# LEDpanelECO.net
KiCad netlist of a schematic drawn in EAGLE
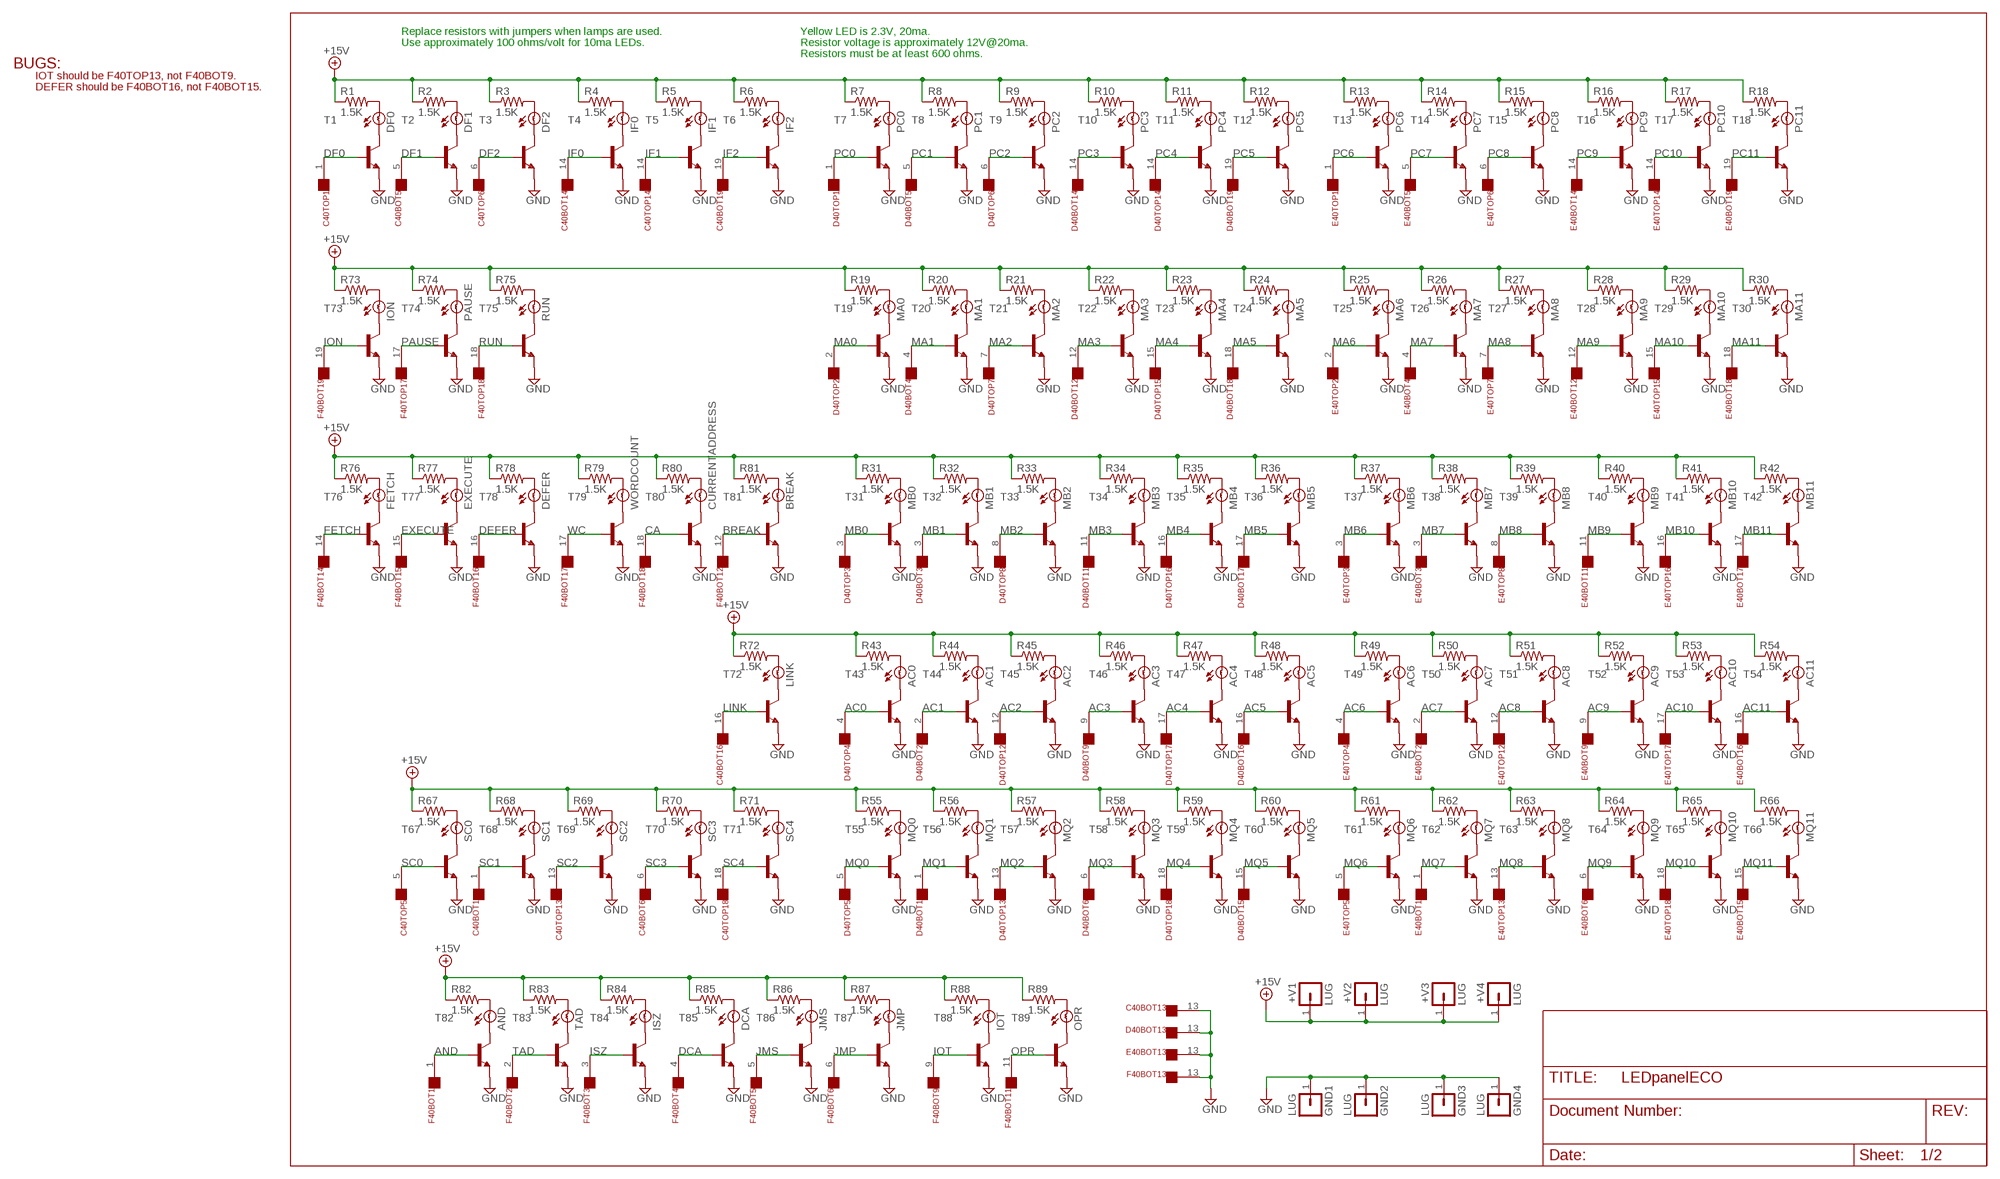
[diagram p0: schematic, sheet 1]
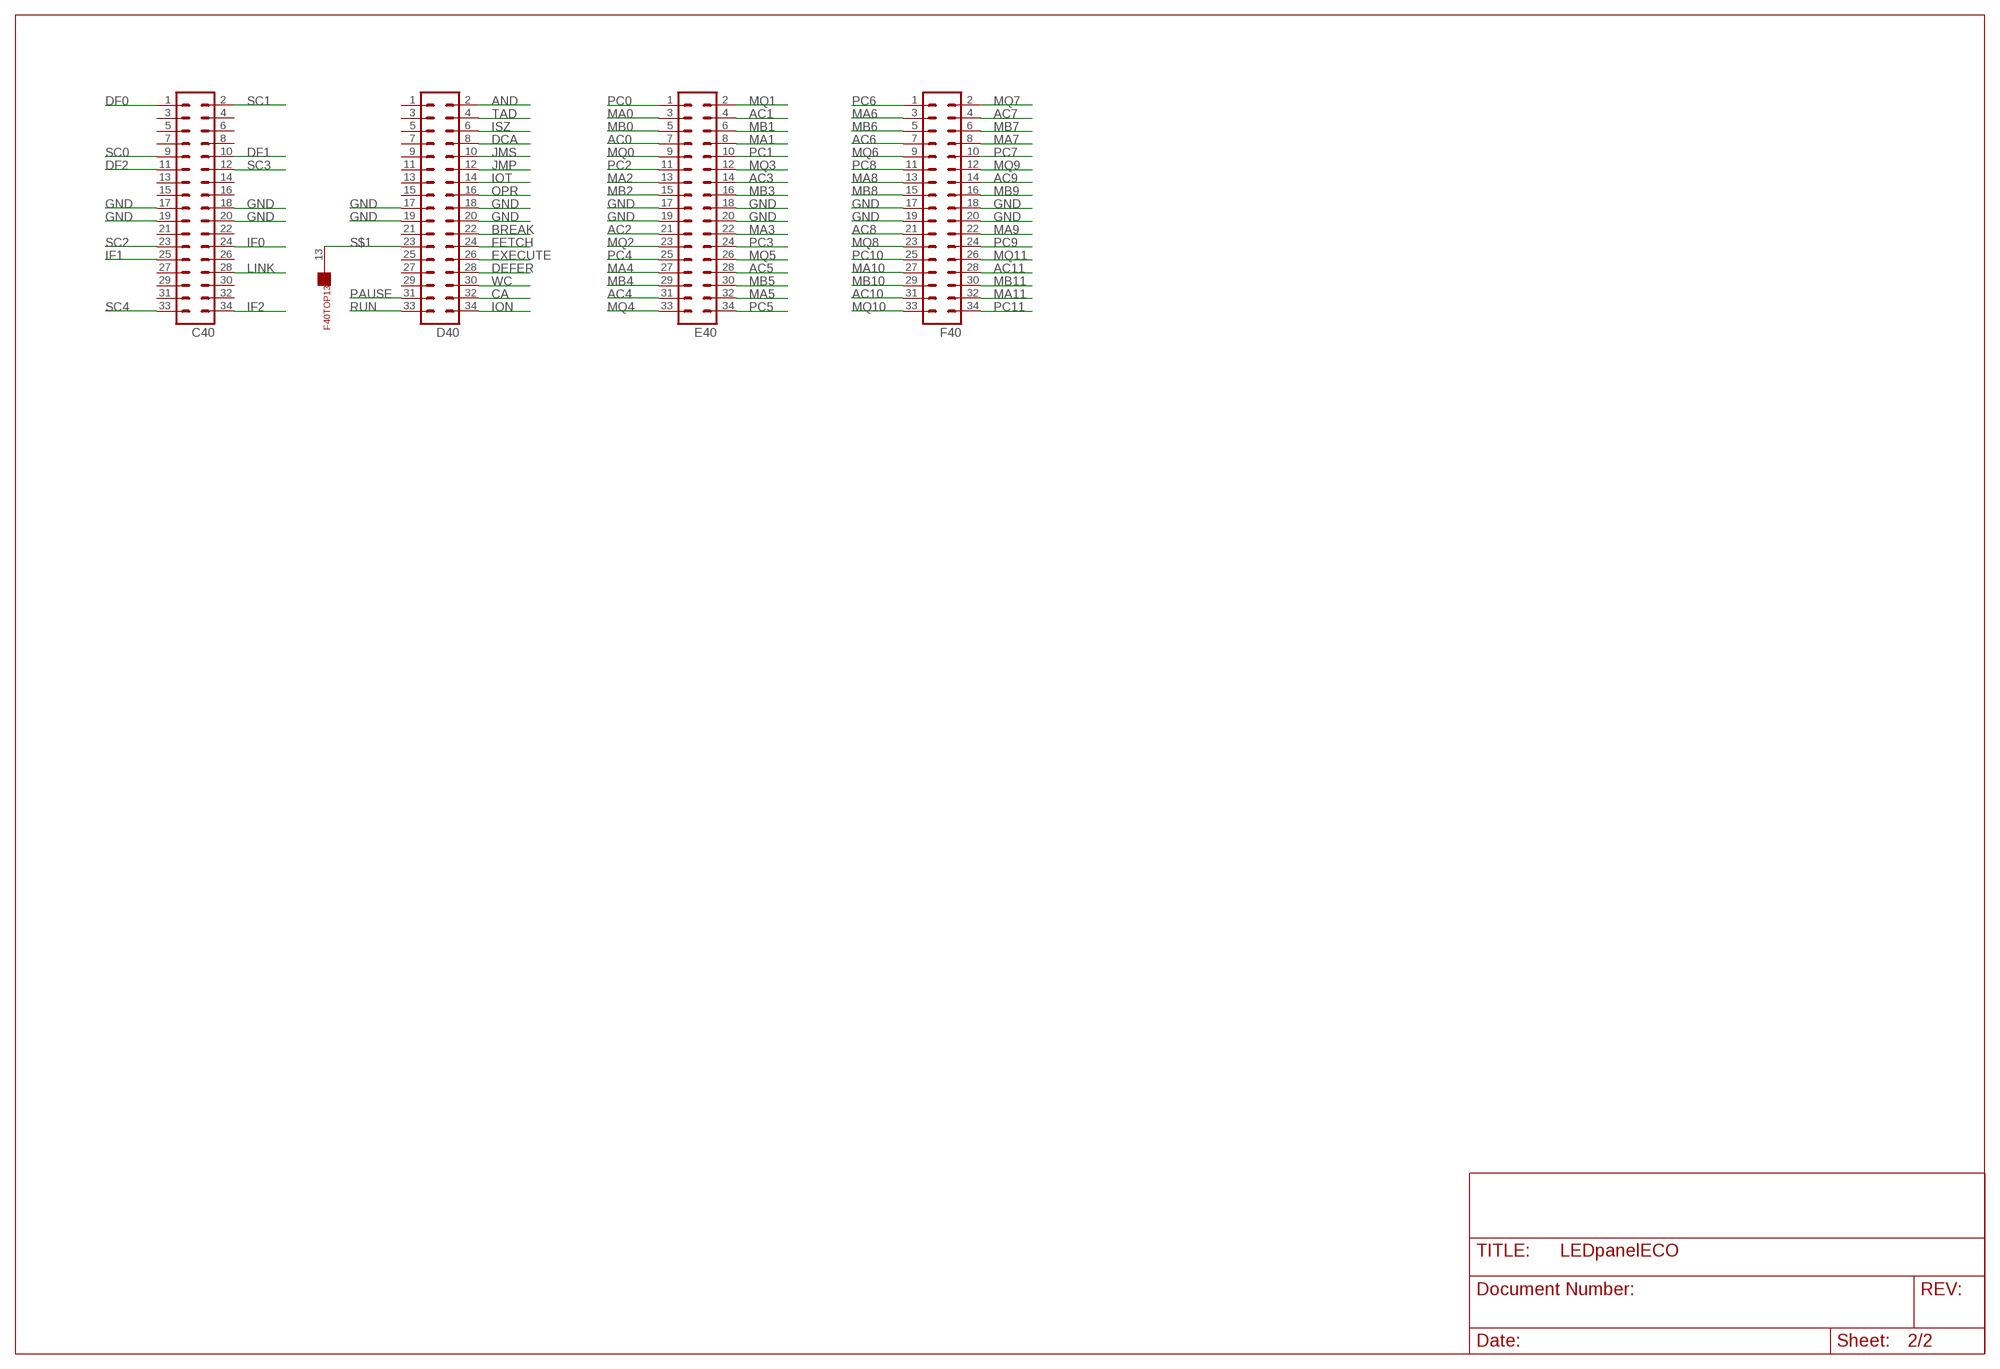
[diagram p1: schematic, sheet 2]

(export (version "E")
  (design (tool "Eeschema 10.0.6"))
  (components
    (comp (ref "C40")
      (value "ML34")
      (footprint "eagle-import:ML34")
      (libsource (lib "eagle-import") (part "ML34"))
    )
    (comp (ref "D40")
      (value "ML34")
      (footprint "eagle-import:ML34")
      (libsource (lib "eagle-import") (part "ML34"))
    )
    (comp (ref "E40")
      (value "ML34")
      (footprint "eagle-import:ML34")
      (libsource (lib "eagle-import") (part "ML34"))
    )
    (comp (ref "F40")
      (value "ML34")
      (footprint "eagle-import:ML34")
      (libsource (lib "eagle-import") (part "ML34"))
    )
    (comp (ref "F40TOP")
      (value "FLEX19")
      (footprint "eagle-import:FLEX19")
      (libsource (lib "eagle-import") (part "FLEX19"))
    )
    (comp (ref "+V1")
      (value "LUG")
      (footprint "eagle-import:SPADELUG")
      (libsource (lib "eagle-import") (part "LUG"))
    )
    (comp (ref "+V2")
      (value "LUG")
      (footprint "eagle-import:SPADELUG")
      (libsource (lib "eagle-import") (part "LUG"))
    )
    (comp (ref "+V3")
      (value "LUG")
      (footprint "eagle-import:SPADELUG")
      (libsource (lib "eagle-import") (part "LUG"))
    )
    (comp (ref "+V4")
      (value "LUG")
      (footprint "eagle-import:SPADELUG")
      (libsource (lib "eagle-import") (part "LUG"))
    )
    (comp (ref "AC0")
      (value "BULB")
      (footprint "eagle-import:BULB")
      (libsource (lib "eagle-import") (part "BULB"))
    )
    (comp (ref "AC1")
      (value "BULB")
      (footprint "eagle-import:BULB")
      (libsource (lib "eagle-import") (part "BULB"))
    )
    (comp (ref "AC2")
      (value "BULB")
      (footprint "eagle-import:BULB")
      (libsource (lib "eagle-import") (part "BULB"))
    )
    (comp (ref "AC3")
      (value "BULB")
      (footprint "eagle-import:BULB")
      (libsource (lib "eagle-import") (part "BULB"))
    )
    (comp (ref "AC4")
      (value "BULB")
      (footprint "eagle-import:BULB")
      (libsource (lib "eagle-import") (part "BULB"))
    )
    (comp (ref "AC5")
      (value "BULB")
      (footprint "eagle-import:BULB")
      (libsource (lib "eagle-import") (part "BULB"))
    )
    (comp (ref "AC6")
      (value "BULB")
      (footprint "eagle-import:BULB")
      (libsource (lib "eagle-import") (part "BULB"))
    )
    (comp (ref "AC7")
      (value "BULB")
      (footprint "eagle-import:BULB")
      (libsource (lib "eagle-import") (part "BULB"))
    )
    (comp (ref "AC8")
      (value "BULB")
      (footprint "eagle-import:BULB")
      (libsource (lib "eagle-import") (part "BULB"))
    )
    (comp (ref "AC9")
      (value "BULB")
      (footprint "eagle-import:BULB")
      (libsource (lib "eagle-import") (part "BULB"))
    )
    (comp (ref "AC10")
      (value "BULB")
      (footprint "eagle-import:BULB")
      (libsource (lib "eagle-import") (part "BULB"))
    )
    (comp (ref "AC11")
      (value "BULB")
      (footprint "eagle-import:BULB")
      (libsource (lib "eagle-import") (part "BULB"))
    )
    (comp (ref "AND")
      (value "BULB")
      (footprint "eagle-import:BULB")
      (libsource (lib "eagle-import") (part "BULB"))
    )
    (comp (ref "BREAK")
      (value "BULB")
      (footprint "eagle-import:BULB")
      (libsource (lib "eagle-import") (part "BULB"))
    )
    (comp (ref "C40BOT")
      (value "FLEX19")
      (footprint "eagle-import:FLEX19")
      (libsource (lib "eagle-import") (part "FLEX19"))
    )
    (comp (ref "C40TOP")
      (value "FLEX19")
      (footprint "eagle-import:FLEX19")
      (libsource (lib "eagle-import") (part "FLEX19"))
    )
    (comp (ref "CURRENTADDRESS")
      (value "BULB")
      (footprint "eagle-import:BULB")
      (libsource (lib "eagle-import") (part "BULB"))
    )
    (comp (ref "D40BOT")
      (value "FLEX19")
      (footprint "eagle-import:FLEX19")
      (libsource (lib "eagle-import") (part "FLEX19"))
    )
    (comp (ref "D40TOP")
      (value "FLEX19")
      (footprint "eagle-import:FLEX19")
      (libsource (lib "eagle-import") (part "FLEX19"))
    )
    (comp (ref "DCA")
      (value "BULB")
      (footprint "eagle-import:BULB")
      (libsource (lib "eagle-import") (part "BULB"))
    )
    (comp (ref "DEFER")
      (value "BULB")
      (footprint "eagle-import:BULB")
      (libsource (lib "eagle-import") (part "BULB"))
    )
    (comp (ref "DF0")
      (value "BULB")
      (footprint "eagle-import:BULB")
      (libsource (lib "eagle-import") (part "BULB"))
    )
    (comp (ref "DF1")
      (value "BULB")
      (footprint "eagle-import:BULB")
      (libsource (lib "eagle-import") (part "BULB"))
    )
    (comp (ref "DF2")
      (value "BULB")
      (footprint "eagle-import:BULB")
      (libsource (lib "eagle-import") (part "BULB"))
    )
    (comp (ref "E40BOT")
      (value "FLEX19")
      (footprint "eagle-import:FLEX19")
      (libsource (lib "eagle-import") (part "FLEX19"))
    )
    (comp (ref "E40TOP")
      (value "FLEX19")
      (footprint "eagle-import:FLEX19")
      (libsource (lib "eagle-import") (part "FLEX19"))
    )
    (comp (ref "EXECUTE")
      (value "BULB")
      (footprint "eagle-import:BULB")
      (libsource (lib "eagle-import") (part "BULB"))
    )
    (comp (ref "F40BOT")
      (value "FLEX19")
      (footprint "eagle-import:FLEX19")
      (libsource (lib "eagle-import") (part "FLEX19"))
    )
    (comp (ref "FETCH")
      (value "BULB")
      (footprint "eagle-import:BULB")
      (libsource (lib "eagle-import") (part "BULB"))
    )
    (comp (ref "GND1")
      (value "LUG")
      (footprint "eagle-import:SPADELUG")
      (libsource (lib "eagle-import") (part "LUG"))
    )
    (comp (ref "GND2")
      (value "LUG")
      (footprint "eagle-import:SPADELUG")
      (libsource (lib "eagle-import") (part "LUG"))
    )
    (comp (ref "GND3")
      (value "LUG")
      (footprint "eagle-import:SPADELUG")
      (libsource (lib "eagle-import") (part "LUG"))
    )
    (comp (ref "GND4")
      (value "LUG")
      (footprint "eagle-import:SPADELUG")
      (libsource (lib "eagle-import") (part "LUG"))
    )
    (comp (ref "IF0")
      (value "BULB")
      (footprint "eagle-import:BULB")
      (libsource (lib "eagle-import") (part "BULB"))
    )
    (comp (ref "IF1")
      (value "BULB")
      (footprint "eagle-import:BULB")
      (libsource (lib "eagle-import") (part "BULB"))
    )
    (comp (ref "IF2")
      (value "BULB")
      (footprint "eagle-import:BULB")
      (libsource (lib "eagle-import") (part "BULB"))
    )
    (comp (ref "ION")
      (value "BULB")
      (footprint "eagle-import:BULB")
      (libsource (lib "eagle-import") (part "BULB"))
    )
    (comp (ref "IOT")
      (value "BULB")
      (footprint "eagle-import:BULB")
      (libsource (lib "eagle-import") (part "BULB"))
    )
    (comp (ref "ISZ")
      (value "BULB")
      (footprint "eagle-import:BULB")
      (libsource (lib "eagle-import") (part "BULB"))
    )
    (comp (ref "JMP")
      (value "BULB")
      (footprint "eagle-import:BULB")
      (libsource (lib "eagle-import") (part "BULB"))
    )
    (comp (ref "JMS")
      (value "BULB")
      (footprint "eagle-import:BULB")
      (libsource (lib "eagle-import") (part "BULB"))
    )
    (comp (ref "LINK")
      (value "BULB")
      (footprint "eagle-import:BULB")
      (libsource (lib "eagle-import") (part "BULB"))
    )
    (comp (ref "MA0")
      (value "BULB")
      (footprint "eagle-import:BULB")
      (libsource (lib "eagle-import") (part "BULB"))
    )
    (comp (ref "MA1")
      (value "BULB")
      (footprint "eagle-import:BULB")
      (libsource (lib "eagle-import") (part "BULB"))
    )
    (comp (ref "MA2")
      (value "BULB")
      (footprint "eagle-import:BULB")
      (libsource (lib "eagle-import") (part "BULB"))
    )
    (comp (ref "MA3")
      (value "BULB")
      (footprint "eagle-import:BULB")
      (libsource (lib "eagle-import") (part "BULB"))
    )
    (comp (ref "MA4")
      (value "BULB")
      (footprint "eagle-import:BULB")
      (libsource (lib "eagle-import") (part "BULB"))
    )
    (comp (ref "MA5")
      (value "BULB")
      (footprint "eagle-import:BULB")
      (libsource (lib "eagle-import") (part "BULB"))
    )
    (comp (ref "MA6")
      (value "BULB")
      (footprint "eagle-import:BULB")
      (libsource (lib "eagle-import") (part "BULB"))
    )
    (comp (ref "MA7")
      (value "BULB")
      (footprint "eagle-import:BULB")
      (libsource (lib "eagle-import") (part "BULB"))
    )
    (comp (ref "MA8")
      (value "BULB")
      (footprint "eagle-import:BULB")
      (libsource (lib "eagle-import") (part "BULB"))
    )
    (comp (ref "MA9")
      (value "BULB")
      (footprint "eagle-import:BULB")
      (libsource (lib "eagle-import") (part "BULB"))
    )
    (comp (ref "MA10")
      (value "BULB")
      (footprint "eagle-import:BULB")
      (libsource (lib "eagle-import") (part "BULB"))
    )
    (comp (ref "MA11")
      (value "BULB")
      (footprint "eagle-import:BULB")
      (libsource (lib "eagle-import") (part "BULB"))
    )
    (comp (ref "MB0")
      (value "BULB")
      (footprint "eagle-import:BULB")
      (libsource (lib "eagle-import") (part "BULB"))
    )
    (comp (ref "MB1")
      (value "BULB")
      (footprint "eagle-import:BULB")
      (libsource (lib "eagle-import") (part "BULB"))
    )
    (comp (ref "MB2")
      (value "BULB")
      (footprint "eagle-import:BULB")
      (libsource (lib "eagle-import") (part "BULB"))
    )
    (comp (ref "MB3")
      (value "BULB")
      (footprint "eagle-import:BULB")
      (libsource (lib "eagle-import") (part "BULB"))
    )
    (comp (ref "MB4")
      (value "BULB")
      (footprint "eagle-import:BULB")
      (libsource (lib "eagle-import") (part "BULB"))
    )
    (comp (ref "MB5")
      (value "BULB")
      (footprint "eagle-import:BULB")
      (libsource (lib "eagle-import") (part "BULB"))
    )
    (comp (ref "MB6")
      (value "BULB")
      (footprint "eagle-import:BULB")
      (libsource (lib "eagle-import") (part "BULB"))
    )
    (comp (ref "MB7")
      (value "BULB")
      (footprint "eagle-import:BULB")
      (libsource (lib "eagle-import") (part "BULB"))
    )
    (comp (ref "MB8")
      (value "BULB")
      (footprint "eagle-import:BULB")
      (libsource (lib "eagle-import") (part "BULB"))
    )
    (comp (ref "MB9")
      (value "BULB")
      (footprint "eagle-import:BULB")
      (libsource (lib "eagle-import") (part "BULB"))
    )
    (comp (ref "MB10")
      (value "BULB")
      (footprint "eagle-import:BULB")
      (libsource (lib "eagle-import") (part "BULB"))
    )
    (comp (ref "MB11")
      (value "BULB")
      (footprint "eagle-import:BULB")
      (libsource (lib "eagle-import") (part "BULB"))
    )
    (comp (ref "MQ0")
      (value "BULB")
      (footprint "eagle-import:BULB")
      (libsource (lib "eagle-import") (part "BULB"))
    )
    (comp (ref "MQ1")
      (value "BULB")
      (footprint "eagle-import:BULB")
      (libsource (lib "eagle-import") (part "BULB"))
    )
    (comp (ref "MQ2")
      (value "BULB")
      (footprint "eagle-import:BULB")
      (libsource (lib "eagle-import") (part "BULB"))
    )
    (comp (ref "MQ3")
      (value "BULB")
      (footprint "eagle-import:BULB")
      (libsource (lib "eagle-import") (part "BULB"))
    )
    (comp (ref "MQ4")
      (value "BULB")
      (footprint "eagle-import:BULB")
      (libsource (lib "eagle-import") (part "BULB"))
    )
    (comp (ref "MQ5")
      (value "BULB")
      (footprint "eagle-import:BULB")
      (libsource (lib "eagle-import") (part "BULB"))
    )
    (comp (ref "MQ6")
      (value "BULB")
      (footprint "eagle-import:BULB")
      (libsource (lib "eagle-import") (part "BULB"))
    )
    (comp (ref "MQ7")
      (value "BULB")
      (footprint "eagle-import:BULB")
      (libsource (lib "eagle-import") (part "BULB"))
    )
    (comp (ref "MQ8")
      (value "BULB")
      (footprint "eagle-import:BULB")
      (libsource (lib "eagle-import") (part "BULB"))
    )
    (comp (ref "MQ9")
      (value "BULB")
      (footprint "eagle-import:BULB")
      (libsource (lib "eagle-import") (part "BULB"))
    )
    (comp (ref "MQ10")
      (value "BULB")
      (footprint "eagle-import:BULB")
      (libsource (lib "eagle-import") (part "BULB"))
    )
    (comp (ref "MQ11")
      (value "BULB")
      (footprint "eagle-import:BULB")
      (libsource (lib "eagle-import") (part "BULB"))
    )
    (comp (ref "OPR")
      (value "BULB")
      (footprint "eagle-import:BULB")
      (libsource (lib "eagle-import") (part "BULB"))
    )
    (comp (ref "PAUSE")
      (value "BULB")
      (footprint "eagle-import:BULB")
      (libsource (lib "eagle-import") (part "BULB"))
    )
    (comp (ref "PC0")
      (value "BULB")
      (footprint "eagle-import:BULB")
      (libsource (lib "eagle-import") (part "BULB"))
    )
    (comp (ref "PC1")
      (value "BULB")
      (footprint "eagle-import:BULB")
      (libsource (lib "eagle-import") (part "BULB"))
    )
    (comp (ref "PC2")
      (value "BULB")
      (footprint "eagle-import:BULB")
      (libsource (lib "eagle-import") (part "BULB"))
    )
    (comp (ref "PC3")
      (value "BULB")
      (footprint "eagle-import:BULB")
      (libsource (lib "eagle-import") (part "BULB"))
    )
    (comp (ref "PC4")
      (value "BULB")
      (footprint "eagle-import:BULB")
      (libsource (lib "eagle-import") (part "BULB"))
    )
    (comp (ref "PC5")
      (value "BULB")
      (footprint "eagle-import:BULB")
      (libsource (lib "eagle-import") (part "BULB"))
    )
    (comp (ref "PC6")
      (value "BULB")
      (footprint "eagle-import:BULB")
      (libsource (lib "eagle-import") (part "BULB"))
    )
    (comp (ref "PC7")
      (value "BULB")
      (footprint "eagle-import:BULB")
      (libsource (lib "eagle-import") (part "BULB"))
    )
    (comp (ref "PC8")
      (value "BULB")
      (footprint "eagle-import:BULB")
      (libsource (lib "eagle-import") (part "BULB"))
    )
    (comp (ref "PC9")
      (value "BULB")
      (footprint "eagle-import:BULB")
      (libsource (lib "eagle-import") (part "BULB"))
    )
    (comp (ref "PC10")
      (value "BULB")
      (footprint "eagle-import:BULB")
      (libsource (lib "eagle-import") (part "BULB"))
    )
    (comp (ref "PC11")
      (value "BULB")
      (footprint "eagle-import:BULB")
      (libsource (lib "eagle-import") (part "BULB"))
    )
    (comp (ref "R1")
      (value "1.5K")
      (footprint "eagle-import:0207_10")
      (libsource (lib "eagle-import") (part "R-US_0207/10"))
    )
    (comp (ref "R2")
      (value "1.5K")
      (footprint "eagle-import:0207_10")
      (libsource (lib "eagle-import") (part "R-US_0207/10"))
    )
    (comp (ref "R3")
      (value "1.5K")
      (footprint "eagle-import:0207_10")
      (libsource (lib "eagle-import") (part "R-US_0207/10"))
    )
    (comp (ref "R4")
      (value "1.5K")
      (footprint "eagle-import:0207_10")
      (libsource (lib "eagle-import") (part "R-US_0207/10"))
    )
    (comp (ref "R5")
      (value "1.5K")
      (footprint "eagle-import:0207_10")
      (libsource (lib "eagle-import") (part "R-US_0207/10"))
    )
    (comp (ref "R6")
      (value "1.5K")
      (footprint "eagle-import:0207_10")
      (libsource (lib "eagle-import") (part "R-US_0207/10"))
    )
    (comp (ref "R7")
      (value "1.5K")
      (footprint "eagle-import:0207_10")
      (libsource (lib "eagle-import") (part "R-US_0207/10"))
    )
    (comp (ref "R8")
      (value "1.5K")
      (footprint "eagle-import:0207_10")
      (libsource (lib "eagle-import") (part "R-US_0207/10"))
    )
    (comp (ref "R9")
      (value "1.5K")
      (footprint "eagle-import:0207_10")
      (libsource (lib "eagle-import") (part "R-US_0207/10"))
    )
    (comp (ref "R10")
      (value "1.5K")
      (footprint "eagle-import:0207_10")
      (libsource (lib "eagle-import") (part "R-US_0207/10"))
    )
    (comp (ref "R11")
      (value "1.5K")
      (footprint "eagle-import:0207_10")
      (libsource (lib "eagle-import") (part "R-US_0207/10"))
    )
    (comp (ref "R12")
      (value "1.5K")
      (footprint "eagle-import:0207_10")
      (libsource (lib "eagle-import") (part "R-US_0207/10"))
    )
    (comp (ref "R13")
      (value "1.5K")
      (footprint "eagle-import:0207_10")
      (libsource (lib "eagle-import") (part "R-US_0207/10"))
    )
    (comp (ref "R14")
      (value "1.5K")
      (footprint "eagle-import:0207_10")
      (libsource (lib "eagle-import") (part "R-US_0207/10"))
    )
    (comp (ref "R15")
      (value "1.5K")
      (footprint "eagle-import:0207_10")
      (libsource (lib "eagle-import") (part "R-US_0207/10"))
    )
    (comp (ref "R16")
      (value "1.5K")
      (footprint "eagle-import:0207_10")
      (libsource (lib "eagle-import") (part "R-US_0207/10"))
    )
    (comp (ref "R17")
      (value "1.5K")
      (footprint "eagle-import:0207_10")
      (libsource (lib "eagle-import") (part "R-US_0207/10"))
    )
    (comp (ref "R18")
      (value "1.5K")
      (footprint "eagle-import:0207_10")
      (libsource (lib "eagle-import") (part "R-US_0207/10"))
    )
    (comp (ref "R19")
      (value "1.5K")
      (footprint "eagle-import:0207_10")
      (libsource (lib "eagle-import") (part "R-US_0207/10"))
    )
    (comp (ref "R20")
      (value "1.5K")
      (footprint "eagle-import:0207_10")
      (libsource (lib "eagle-import") (part "R-US_0207/10"))
    )
    (comp (ref "R21")
      (value "1.5K")
      (footprint "eagle-import:0207_10")
      (libsource (lib "eagle-import") (part "R-US_0207/10"))
    )
    (comp (ref "R22")
      (value "1.5K")
      (footprint "eagle-import:0207_10")
      (libsource (lib "eagle-import") (part "R-US_0207/10"))
    )
    (comp (ref "R23")
      (value "1.5K")
      (footprint "eagle-import:0207_10")
      (libsource (lib "eagle-import") (part "R-US_0207/10"))
    )
    (comp (ref "R24")
      (value "1.5K")
      (footprint "eagle-import:0207_10")
      (libsource (lib "eagle-import") (part "R-US_0207/10"))
    )
    (comp (ref "R25")
      (value "1.5K")
      (footprint "eagle-import:0207_10")
      (libsource (lib "eagle-import") (part "R-US_0207/10"))
    )
    (comp (ref "R26")
      (value "1.5K")
      (footprint "eagle-import:0207_10")
      (libsource (lib "eagle-import") (part "R-US_0207/10"))
    )
    (comp (ref "R27")
      (value "1.5K")
      (footprint "eagle-import:0207_10")
      (libsource (lib "eagle-import") (part "R-US_0207/10"))
    )
    (comp (ref "R28")
      (value "1.5K")
      (footprint "eagle-import:0207_10")
      (libsource (lib "eagle-import") (part "R-US_0207/10"))
    )
    (comp (ref "R29")
      (value "1.5K")
      (footprint "eagle-import:0207_10")
      (libsource (lib "eagle-import") (part "R-US_0207/10"))
    )
    (comp (ref "R30")
      (value "1.5K")
      (footprint "eagle-import:0207_10")
      (libsource (lib "eagle-import") (part "R-US_0207/10"))
    )
    (comp (ref "R31")
      (value "1.5K")
      (footprint "eagle-import:0207_10")
      (libsource (lib "eagle-import") (part "R-US_0207/10"))
    )
    (comp (ref "R32")
      (value "1.5K")
      (footprint "eagle-import:0207_10")
      (libsource (lib "eagle-import") (part "R-US_0207/10"))
    )
    (comp (ref "R33")
      (value "1.5K")
      (footprint "eagle-import:0207_10")
      (libsource (lib "eagle-import") (part "R-US_0207/10"))
    )
    (comp (ref "R34")
      (value "1.5K")
      (footprint "eagle-import:0207_10")
      (libsource (lib "eagle-import") (part "R-US_0207/10"))
    )
    (comp (ref "R35")
      (value "1.5K")
      (footprint "eagle-import:0207_10")
      (libsource (lib "eagle-import") (part "R-US_0207/10"))
    )
    (comp (ref "R36")
      (value "1.5K")
      (footprint "eagle-import:0207_10")
      (libsource (lib "eagle-import") (part "R-US_0207/10"))
    )
    (comp (ref "R37")
      (value "1.5K")
      (footprint "eagle-import:0207_10")
      (libsource (lib "eagle-import") (part "R-US_0207/10"))
    )
    (comp (ref "R38")
      (value "1.5K")
      (footprint "eagle-import:0207_10")
      (libsource (lib "eagle-import") (part "R-US_0207/10"))
    )
    (comp (ref "R39")
      (value "1.5K")
      (footprint "eagle-import:0207_10")
      (libsource (lib "eagle-import") (part "R-US_0207/10"))
    )
    (comp (ref "R40")
      (value "1.5K")
      (footprint "eagle-import:0207_10")
      (libsource (lib "eagle-import") (part "R-US_0207/10"))
    )
    (comp (ref "R41")
      (value "1.5K")
      (footprint "eagle-import:0207_10")
      (libsource (lib "eagle-import") (part "R-US_0207/10"))
    )
    (comp (ref "R42")
      (value "1.5K")
      (footprint "eagle-import:0207_10")
      (libsource (lib "eagle-import") (part "R-US_0207/10"))
    )
    (comp (ref "R43")
      (value "1.5K")
      (footprint "eagle-import:0207_10")
      (libsource (lib "eagle-import") (part "R-US_0207/10"))
    )
    (comp (ref "R44")
      (value "1.5K")
      (footprint "eagle-import:0207_10")
      (libsource (lib "eagle-import") (part "R-US_0207/10"))
    )
    (comp (ref "R45")
      (value "1.5K")
      (footprint "eagle-import:0207_10")
      (libsource (lib "eagle-import") (part "R-US_0207/10"))
    )
    (comp (ref "R46")
      (value "1.5K")
      (footprint "eagle-import:0207_10")
      (libsource (lib "eagle-import") (part "R-US_0207/10"))
    )
    (comp (ref "R47")
      (value "1.5K")
      (footprint "eagle-import:0207_10")
      (libsource (lib "eagle-import") (part "R-US_0207/10"))
    )
    (comp (ref "R48")
      (value "1.5K")
      (footprint "eagle-import:0207_10")
      (libsource (lib "eagle-import") (part "R-US_0207/10"))
    )
    (comp (ref "R49")
      (value "1.5K")
      (footprint "eagle-import:0207_10")
      (libsource (lib "eagle-import") (part "R-US_0207/10"))
    )
    (comp (ref "R50")
      (value "1.5K")
      (footprint "eagle-import:0207_10")
      (libsource (lib "eagle-import") (part "R-US_0207/10"))
    )
    (comp (ref "R51")
      (value "1.5K")
      (footprint "eagle-import:0207_10")
      (libsource (lib "eagle-import") (part "R-US_0207/10"))
    )
    (comp (ref "R52")
      (value "1.5K")
      (footprint "eagle-import:0207_10")
      (libsource (lib "eagle-import") (part "R-US_0207/10"))
    )
    (comp (ref "R53")
      (value "1.5K")
      (footprint "eagle-import:0207_10")
      (libsource (lib "eagle-import") (part "R-US_0207/10"))
    )
    (comp (ref "R54")
      (value "1.5K")
      (footprint "eagle-import:0207_10")
      (libsource (lib "eagle-import") (part "R-US_0207/10"))
    )
    (comp (ref "R55")
      (value "1.5K")
      (footprint "eagle-import:0207_10")
      (libsource (lib "eagle-import") (part "R-US_0207/10"))
    )
    (comp (ref "R56")
      (value "1.5K")
      (footprint "eagle-import:0207_10")
      (libsource (lib "eagle-import") (part "R-US_0207/10"))
    )
    (comp (ref "R57")
      (value "1.5K")
      (footprint "eagle-import:0207_10")
      (libsource (lib "eagle-import") (part "R-US_0207/10"))
    )
    (comp (ref "R58")
      (value "1.5K")
      (footprint "eagle-import:0207_10")
      (libsource (lib "eagle-import") (part "R-US_0207/10"))
    )
    (comp (ref "R59")
      (value "1.5K")
      (footprint "eagle-import:0207_10")
      (libsource (lib "eagle-import") (part "R-US_0207/10"))
    )
    (comp (ref "R60")
      (value "1.5K")
      (footprint "eagle-import:0207_10")
      (libsource (lib "eagle-import") (part "R-US_0207/10"))
    )
    (comp (ref "R61")
      (value "1.5K")
      (footprint "eagle-import:0207_10")
      (libsource (lib "eagle-import") (part "R-US_0207/10"))
    )
    (comp (ref "R62")
      (value "1.5K")
      (footprint "eagle-import:0207_10")
      (libsource (lib "eagle-import") (part "R-US_0207/10"))
    )
    (comp (ref "R63")
      (value "1.5K")
      (footprint "eagle-import:0207_10")
      (libsource (lib "eagle-import") (part "R-US_0207/10"))
    )
    (comp (ref "R64")
      (value "1.5K")
      (footprint "eagle-import:0207_10")
      (libsource (lib "eagle-import") (part "R-US_0207/10"))
    )
    (comp (ref "R65")
      (value "1.5K")
      (footprint "eagle-import:0207_10")
      (libsource (lib "eagle-import") (part "R-US_0207/10"))
    )
    (comp (ref "R66")
      (value "1.5K")
      (footprint "eagle-import:0207_10")
      (libsource (lib "eagle-import") (part "R-US_0207/10"))
    )
    (comp (ref "R67")
      (value "1.5K")
      (footprint "eagle-import:0207_10")
      (libsource (lib "eagle-import") (part "R-US_0207/10"))
    )
    (comp (ref "R68")
      (value "1.5K")
      (footprint "eagle-import:0207_10")
      (libsource (lib "eagle-import") (part "R-US_0207/10"))
    )
    (comp (ref "R69")
      (value "1.5K")
      (footprint "eagle-import:0207_10")
      (libsource (lib "eagle-import") (part "R-US_0207/10"))
    )
    (comp (ref "R70")
      (value "1.5K")
      (footprint "eagle-import:0207_10")
      (libsource (lib "eagle-import") (part "R-US_0207/10"))
    )
    (comp (ref "R71")
      (value "1.5K")
      (footprint "eagle-import:0207_10")
      (libsource (lib "eagle-import") (part "R-US_0207/10"))
    )
    (comp (ref "R72")
      (value "1.5K")
      (footprint "eagle-import:0207_10")
      (libsource (lib "eagle-import") (part "R-US_0207/10"))
    )
    (comp (ref "R73")
      (value "1.5K")
      (footprint "eagle-import:0207_10")
      (libsource (lib "eagle-import") (part "R-US_0207/10"))
    )
    (comp (ref "R74")
      (value "1.5K")
      (footprint "eagle-import:0207_10")
      (libsource (lib "eagle-import") (part "R-US_0207/10"))
    )
    (comp (ref "R75")
      (value "1.5K")
      (footprint "eagle-import:0207_10")
      (libsource (lib "eagle-import") (part "R-US_0207/10"))
    )
    (comp (ref "R76")
      (value "1.5K")
      (footprint "eagle-import:0207_10")
      (libsource (lib "eagle-import") (part "R-US_0207/10"))
    )
    (comp (ref "R77")
      (value "1.5K")
      (footprint "eagle-import:0207_10")
      (libsource (lib "eagle-import") (part "R-US_0207/10"))
    )
    (comp (ref "R78")
      (value "1.5K")
      (footprint "eagle-import:0207_10")
      (libsource (lib "eagle-import") (part "R-US_0207/10"))
    )
    (comp (ref "R79")
      (value "1.5K")
      (footprint "eagle-import:0207_10")
      (libsource (lib "eagle-import") (part "R-US_0207/10"))
    )
    (comp (ref "R80")
      (value "1.5K")
      (footprint "eagle-import:0207_10")
      (libsource (lib "eagle-import") (part "R-US_0207/10"))
    )
    (comp (ref "R81")
      (value "1.5K")
      (footprint "eagle-import:0207_10")
      (libsource (lib "eagle-import") (part "R-US_0207/10"))
    )
    (comp (ref "R82")
      (value "1.5K")
      (footprint "eagle-import:0207_10")
      (libsource (lib "eagle-import") (part "R-US_0207/10"))
    )
    (comp (ref "R83")
      (value "1.5K")
      (footprint "eagle-import:0207_10")
      (libsource (lib "eagle-import") (part "R-US_0207/10"))
    )
    (comp (ref "R84")
      (value "1.5K")
      (footprint "eagle-import:0207_10")
      (libsource (lib "eagle-import") (part "R-US_0207/10"))
    )
    (comp (ref "R85")
      (value "1.5K")
      (footprint "eagle-import:0207_10")
      (libsource (lib "eagle-import") (part "R-US_0207/10"))
    )
    (comp (ref "R86")
      (value "1.5K")
      (footprint "eagle-import:0207_10")
      (libsource (lib "eagle-import") (part "R-US_0207/10"))
    )
    (comp (ref "R87")
      (value "1.5K")
      (footprint "eagle-import:0207_10")
      (libsource (lib "eagle-import") (part "R-US_0207/10"))
    )
    (comp (ref "R88")
      (value "1.5K")
      (footprint "eagle-import:0207_10")
      (libsource (lib "eagle-import") (part "R-US_0207/10"))
    )
    (comp (ref "R89")
      (value "1.5K")
      (footprint "eagle-import:0207_10")
      (libsource (lib "eagle-import") (part "R-US_0207/10"))
    )
    (comp (ref "RUN")
      (value "BULB")
      (footprint "eagle-import:BULB")
      (libsource (lib "eagle-import") (part "BULB"))
    )
    (comp (ref "SC0")
      (value "BULB")
      (footprint "eagle-import:BULB")
      (libsource (lib "eagle-import") (part "BULB"))
    )
    (comp (ref "SC1")
      (value "BULB")
      (footprint "eagle-import:BULB")
      (libsource (lib "eagle-import") (part "BULB"))
    )
    (comp (ref "SC2")
      (value "BULB")
      (footprint "eagle-import:BULB")
      (libsource (lib "eagle-import") (part "BULB"))
    )
    (comp (ref "SC3")
      (value "BULB")
      (footprint "eagle-import:BULB")
      (libsource (lib "eagle-import") (part "BULB"))
    )
    (comp (ref "SC4")
      (value "BULB")
      (footprint "eagle-import:BULB")
      (libsource (lib "eagle-import") (part "BULB"))
    )
    (comp (ref "T1")
      (value "MPS2222A-NPN-TO92-CBE")
      (footprint "eagle-import:TO92-CBE")
      (libsource (lib "eagle-import") (part "-NPN-TO92-CBEMPS2222A"))
    )
    (comp (ref "T2")
      (value "MPS2222A-NPN-TO92-CBE")
      (footprint "eagle-import:TO92-CBE")
      (libsource (lib "eagle-import") (part "-NPN-TO92-CBEMPS2222A"))
    )
    (comp (ref "T3")
      (value "MPS2222A-NPN-TO92-CBE")
      (footprint "eagle-import:TO92-CBE")
      (libsource (lib "eagle-import") (part "-NPN-TO92-CBEMPS2222A"))
    )
    (comp (ref "T4")
      (value "MPS2222A-NPN-TO92-CBE")
      (footprint "eagle-import:TO92-CBE")
      (libsource (lib "eagle-import") (part "-NPN-TO92-CBEMPS2222A"))
    )
    (comp (ref "T5")
      (value "MPS2222A-NPN-TO92-CBE")
      (footprint "eagle-import:TO92-CBE")
      (libsource (lib "eagle-import") (part "-NPN-TO92-CBEMPS2222A"))
    )
    (comp (ref "T6")
      (value "MPS2222A-NPN-TO92-CBE")
      (footprint "eagle-import:TO92-CBE")
      (libsource (lib "eagle-import") (part "-NPN-TO92-CBEMPS2222A"))
    )
    (comp (ref "T7")
      (value "MPS2222A-NPN-TO92-CBE")
      (footprint "eagle-import:TO92-CBE")
      (libsource (lib "eagle-import") (part "-NPN-TO92-CBEMPS2222A"))
    )
    (comp (ref "T8")
      (value "MPS2222A-NPN-TO92-CBE")
      (footprint "eagle-import:TO92-CBE")
      (libsource (lib "eagle-import") (part "-NPN-TO92-CBEMPS2222A"))
    )
    (comp (ref "T9")
      (value "MPS2222A-NPN-TO92-CBE")
      (footprint "eagle-import:TO92-CBE")
      (libsource (lib "eagle-import") (part "-NPN-TO92-CBEMPS2222A"))
    )
    (comp (ref "T10")
      (value "MPS2222A-NPN-TO92-CBE")
      (footprint "eagle-import:TO92-CBE")
      (libsource (lib "eagle-import") (part "-NPN-TO92-CBEMPS2222A"))
    )
    (comp (ref "T11")
      (value "MPS2222A-NPN-TO92-CBE")
      (footprint "eagle-import:TO92-CBE")
      (libsource (lib "eagle-import") (part "-NPN-TO92-CBEMPS2222A"))
    )
    (comp (ref "T12")
      (value "MPS2222A-NPN-TO92-CBE")
      (footprint "eagle-import:TO92-CBE")
      (libsource (lib "eagle-import") (part "-NPN-TO92-CBEMPS2222A"))
    )
    (comp (ref "T13")
      (value "MPS2222A-NPN-TO92-CBE")
      (footprint "eagle-import:TO92-CBE")
      (libsource (lib "eagle-import") (part "-NPN-TO92-CBEMPS2222A"))
    )
    (comp (ref "T14")
      (value "MPS2222A-NPN-TO92-CBE")
      (footprint "eagle-import:TO92-CBE")
      (libsource (lib "eagle-import") (part "-NPN-TO92-CBEMPS2222A"))
    )
    (comp (ref "T15")
      (value "MPS2222A-NPN-TO92-CBE")
      (footprint "eagle-import:TO92-CBE")
      (libsource (lib "eagle-import") (part "-NPN-TO92-CBEMPS2222A"))
    )
    (comp (ref "T16")
      (value "MPS2222A-NPN-TO92-CBE")
      (footprint "eagle-import:TO92-CBE")
      (libsource (lib "eagle-import") (part "-NPN-TO92-CBEMPS2222A"))
    )
    (comp (ref "T17")
      (value "MPS2222A-NPN-TO92-CBE")
      (footprint "eagle-import:TO92-CBE")
      (libsource (lib "eagle-import") (part "-NPN-TO92-CBEMPS2222A"))
    )
    (comp (ref "T18")
      (value "MPS2222A-NPN-TO92-CBE")
      (footprint "eagle-import:TO92-CBE")
      (libsource (lib "eagle-import") (part "-NPN-TO92-CBEMPS2222A"))
    )
    (comp (ref "T19")
      (value "MPS2222A-NPN-TO92-CBE")
      (footprint "eagle-import:TO92-CBE")
      (libsource (lib "eagle-import") (part "-NPN-TO92-CBEMPS2222A"))
    )
    (comp (ref "T20")
      (value "MPS2222A-NPN-TO92-CBE")
      (footprint "eagle-import:TO92-CBE")
      (libsource (lib "eagle-import") (part "-NPN-TO92-CBEMPS2222A"))
    )
    (comp (ref "T21")
      (value "MPS2222A-NPN-TO92-CBE")
      (footprint "eagle-import:TO92-CBE")
      (libsource (lib "eagle-import") (part "-NPN-TO92-CBEMPS2222A"))
    )
    (comp (ref "T22")
      (value "MPS2222A-NPN-TO92-CBE")
      (footprint "eagle-import:TO92-CBE")
      (libsource (lib "eagle-import") (part "-NPN-TO92-CBEMPS2222A"))
    )
    (comp (ref "T23")
      (value "MPS2222A-NPN-TO92-CBE")
      (footprint "eagle-import:TO92-CBE")
      (libsource (lib "eagle-import") (part "-NPN-TO92-CBEMPS2222A"))
    )
    (comp (ref "T24")
      (value "MPS2222A-NPN-TO92-CBE")
      (footprint "eagle-import:TO92-CBE")
      (libsource (lib "eagle-import") (part "-NPN-TO92-CBEMPS2222A"))
    )
    (comp (ref "T25")
      (value "MPS2222A-NPN-TO92-CBE")
      (footprint "eagle-import:TO92-CBE")
      (libsource (lib "eagle-import") (part "-NPN-TO92-CBEMPS2222A"))
    )
    (comp (ref "T26")
      (value "MPS2222A-NPN-TO92-CBE")
      (footprint "eagle-import:TO92-CBE")
      (libsource (lib "eagle-import") (part "-NPN-TO92-CBEMPS2222A"))
    )
    (comp (ref "T27")
      (value "MPS2222A-NPN-TO92-CBE")
      (footprint "eagle-import:TO92-CBE")
      (libsource (lib "eagle-import") (part "-NPN-TO92-CBEMPS2222A"))
    )
    (comp (ref "T28")
      (value "MPS2222A-NPN-TO92-CBE")
      (footprint "eagle-import:TO92-CBE")
      (libsource (lib "eagle-import") (part "-NPN-TO92-CBEMPS2222A"))
    )
    (comp (ref "T29")
      (value "MPS2222A-NPN-TO92-CBE")
      (footprint "eagle-import:TO92-CBE")
      (libsource (lib "eagle-import") (part "-NPN-TO92-CBEMPS2222A"))
    )
    (comp (ref "T30")
      (value "MPS2222A-NPN-TO92-CBE")
      (footprint "eagle-import:TO92-CBE")
      (libsource (lib "eagle-import") (part "-NPN-TO92-CBEMPS2222A"))
    )
    (comp (ref "T31")
      (value "MPS2222A-NPN-TO92-CBE")
      (footprint "eagle-import:TO92-CBE")
      (libsource (lib "eagle-import") (part "-NPN-TO92-CBEMPS2222A"))
    )
    (comp (ref "T32")
      (value "MPS2222A-NPN-TO92-CBE")
      (footprint "eagle-import:TO92-CBE")
      (libsource (lib "eagle-import") (part "-NPN-TO92-CBEMPS2222A"))
    )
    (comp (ref "T33")
      (value "MPS2222A-NPN-TO92-CBE")
      (footprint "eagle-import:TO92-CBE")
      (libsource (lib "eagle-import") (part "-NPN-TO92-CBEMPS2222A"))
    )
    (comp (ref "T34")
      (value "MPS2222A-NPN-TO92-CBE")
      (footprint "eagle-import:TO92-CBE")
      (libsource (lib "eagle-import") (part "-NPN-TO92-CBEMPS2222A"))
    )
    (comp (ref "T35")
      (value "MPS2222A-NPN-TO92-CBE")
      (footprint "eagle-import:TO92-CBE")
      (libsource (lib "eagle-import") (part "-NPN-TO92-CBEMPS2222A"))
    )
    (comp (ref "T36")
      (value "MPS2222A-NPN-TO92-CBE")
      (footprint "eagle-import:TO92-CBE")
      (libsource (lib "eagle-import") (part "-NPN-TO92-CBEMPS2222A"))
    )
    (comp (ref "T37")
      (value "MPS2222A-NPN-TO92-CBE")
      (footprint "eagle-import:TO92-CBE")
      (libsource (lib "eagle-import") (part "-NPN-TO92-CBEMPS2222A"))
    )
    (comp (ref "T38")
      (value "MPS2222A-NPN-TO92-CBE")
      (footprint "eagle-import:TO92-CBE")
      (libsource (lib "eagle-import") (part "-NPN-TO92-CBEMPS2222A"))
    )
    (comp (ref "T39")
      (value "MPS2222A-NPN-TO92-CBE")
      (footprint "eagle-import:TO92-CBE")
      (libsource (lib "eagle-import") (part "-NPN-TO92-CBEMPS2222A"))
    )
    (comp (ref "T40")
      (value "MPS2222A-NPN-TO92-CBE")
      (footprint "eagle-import:TO92-CBE")
      (libsource (lib "eagle-import") (part "-NPN-TO92-CBEMPS2222A"))
    )
    (comp (ref "T41")
      (value "MPS2222A-NPN-TO92-CBE")
      (footprint "eagle-import:TO92-CBE")
      (libsource (lib "eagle-import") (part "-NPN-TO92-CBEMPS2222A"))
    )
    (comp (ref "T42")
      (value "MPS2222A-NPN-TO92-CBE")
      (footprint "eagle-import:TO92-CBE")
      (libsource (lib "eagle-import") (part "-NPN-TO92-CBEMPS2222A"))
    )
    (comp (ref "T43")
      (value "MPS2222A-NPN-TO92-CBE")
      (footprint "eagle-import:TO92-CBE")
      (libsource (lib "eagle-import") (part "-NPN-TO92-CBEMPS2222A"))
    )
    (comp (ref "T44")
      (value "MPS2222A-NPN-TO92-CBE")
      (footprint "eagle-import:TO92-CBE")
      (libsource (lib "eagle-import") (part "-NPN-TO92-CBEMPS2222A"))
    )
    (comp (ref "T45")
      (value "MPS2222A-NPN-TO92-CBE")
      (footprint "eagle-import:TO92-CBE")
      (libsource (lib "eagle-import") (part "-NPN-TO92-CBEMPS2222A"))
    )
    (comp (ref "T46")
      (value "MPS2222A-NPN-TO92-CBE")
      (footprint "eagle-import:TO92-CBE")
      (libsource (lib "eagle-import") (part "-NPN-TO92-CBEMPS2222A"))
    )
    (comp (ref "T47")
      (value "MPS2222A-NPN-TO92-CBE")
      (footprint "eagle-import:TO92-CBE")
      (libsource (lib "eagle-import") (part "-NPN-TO92-CBEMPS2222A"))
    )
    (comp (ref "T48")
      (value "MPS2222A-NPN-TO92-CBE")
      (footprint "eagle-import:TO92-CBE")
      (libsource (lib "eagle-import") (part "-NPN-TO92-CBEMPS2222A"))
    )
    (comp (ref "T49")
      (value "MPS2222A-NPN-TO92-CBE")
      (footprint "eagle-import:TO92-CBE")
      (libsource (lib "eagle-import") (part "-NPN-TO92-CBEMPS2222A"))
    )
    (comp (ref "T50")
      (value "MPS2222A-NPN-TO92-CBE")
      (footprint "eagle-import:TO92-CBE")
      (libsource (lib "eagle-import") (part "-NPN-TO92-CBEMPS2222A"))
    )
    (comp (ref "T51")
      (value "MPS2222A-NPN-TO92-CBE")
      (footprint "eagle-import:TO92-CBE")
      (libsource (lib "eagle-import") (part "-NPN-TO92-CBEMPS2222A"))
    )
    (comp (ref "T52")
      (value "MPS2222A-NPN-TO92-CBE")
      (footprint "eagle-import:TO92-CBE")
      (libsource (lib "eagle-import") (part "-NPN-TO92-CBEMPS2222A"))
    )
    (comp (ref "T53")
      (value "MPS2222A-NPN-TO92-CBE")
      (footprint "eagle-import:TO92-CBE")
      (libsource (lib "eagle-import") (part "-NPN-TO92-CBEMPS2222A"))
    )
    (comp (ref "T54")
      (value "MPS2222A-NPN-TO92-CBE")
      (footprint "eagle-import:TO92-CBE")
      (libsource (lib "eagle-import") (part "-NPN-TO92-CBEMPS2222A"))
    )
    (comp (ref "T55")
      (value "MPS2222A-NPN-TO92-CBE")
      (footprint "eagle-import:TO92-CBE")
      (libsource (lib "eagle-import") (part "-NPN-TO92-CBEMPS2222A"))
    )
    (comp (ref "T56")
      (value "MPS2222A-NPN-TO92-CBE")
      (footprint "eagle-import:TO92-CBE")
      (libsource (lib "eagle-import") (part "-NPN-TO92-CBEMPS2222A"))
    )
    (comp (ref "T57")
      (value "MPS2222A-NPN-TO92-CBE")
      (footprint "eagle-import:TO92-CBE")
      (libsource (lib "eagle-import") (part "-NPN-TO92-CBEMPS2222A"))
    )
    (comp (ref "T58")
      (value "MPS2222A-NPN-TO92-CBE")
      (footprint "eagle-import:TO92-CBE")
      (libsource (lib "eagle-import") (part "-NPN-TO92-CBEMPS2222A"))
    )
    (comp (ref "T59")
      (value "MPS2222A-NPN-TO92-CBE")
      (footprint "eagle-import:TO92-CBE")
      (libsource (lib "eagle-import") (part "-NPN-TO92-CBEMPS2222A"))
    )
    (comp (ref "T60")
      (value "MPS2222A-NPN-TO92-CBE")
      (footprint "eagle-import:TO92-CBE")
      (libsource (lib "eagle-import") (part "-NPN-TO92-CBEMPS2222A"))
    )
    (comp (ref "T61")
      (value "MPS2222A-NPN-TO92-CBE")
      (footprint "eagle-import:TO92-CBE")
      (libsource (lib "eagle-import") (part "-NPN-TO92-CBEMPS2222A"))
    )
    (comp (ref "T62")
      (value "MPS2222A-NPN-TO92-CBE")
      (footprint "eagle-import:TO92-CBE")
      (libsource (lib "eagle-import") (part "-NPN-TO92-CBEMPS2222A"))
    )
    (comp (ref "T63")
      (value "MPS2222A-NPN-TO92-CBE")
      (footprint "eagle-import:TO92-CBE")
      (libsource (lib "eagle-import") (part "-NPN-TO92-CBEMPS2222A"))
    )
    (comp (ref "T64")
      (value "MPS2222A-NPN-TO92-CBE")
      (footprint "eagle-import:TO92-CBE")
      (libsource (lib "eagle-import") (part "-NPN-TO92-CBEMPS2222A"))
    )
    (comp (ref "T65")
      (value "MPS2222A-NPN-TO92-CBE")
      (footprint "eagle-import:TO92-CBE")
      (libsource (lib "eagle-import") (part "-NPN-TO92-CBEMPS2222A"))
    )
    (comp (ref "T66")
      (value "MPS2222A-NPN-TO92-CBE")
      (footprint "eagle-import:TO92-CBE")
      (libsource (lib "eagle-import") (part "-NPN-TO92-CBEMPS2222A"))
    )
    (comp (ref "T67")
      (value "MPS2222A-NPN-TO92-CBE")
      (footprint "eagle-import:TO92-CBE")
      (libsource (lib "eagle-import") (part "-NPN-TO92-CBEMPS2222A"))
    )
    (comp (ref "T68")
      (value "MPS2222A-NPN-TO92-CBE")
      (footprint "eagle-import:TO92-CBE")
      (libsource (lib "eagle-import") (part "-NPN-TO92-CBEMPS2222A"))
    )
    (comp (ref "T69")
      (value "MPS2222A-NPN-TO92-CBE")
      (footprint "eagle-import:TO92-CBE")
      (libsource (lib "eagle-import") (part "-NPN-TO92-CBEMPS2222A"))
    )
    (comp (ref "T70")
      (value "MPS2222A-NPN-TO92-CBE")
      (footprint "eagle-import:TO92-CBE")
      (libsource (lib "eagle-import") (part "-NPN-TO92-CBEMPS2222A"))
    )
    (comp (ref "T71")
      (value "MPS2222A-NPN-TO92-CBE")
      (footprint "eagle-import:TO92-CBE")
      (libsource (lib "eagle-import") (part "-NPN-TO92-CBEMPS2222A"))
    )
    (comp (ref "T72")
      (value "MPS2222A-NPN-TO92-CBE")
      (footprint "eagle-import:TO92-CBE")
      (libsource (lib "eagle-import") (part "-NPN-TO92-CBEMPS2222A"))
    )
    (comp (ref "T73")
      (value "MPS2222A-NPN-TO92-CBE")
      (footprint "eagle-import:TO92-CBE")
      (libsource (lib "eagle-import") (part "-NPN-TO92-CBEMPS2222A"))
    )
    (comp (ref "T74")
      (value "MPS2222A-NPN-TO92-CBE")
      (footprint "eagle-import:TO92-CBE")
      (libsource (lib "eagle-import") (part "-NPN-TO92-CBEMPS2222A"))
    )
    (comp (ref "T75")
      (value "MPS2222A-NPN-TO92-CBE")
      (footprint "eagle-import:TO92-CBE")
      (libsource (lib "eagle-import") (part "-NPN-TO92-CBEMPS2222A"))
    )
    (comp (ref "T76")
      (value "MPS2222A-NPN-TO92-CBE")
      (footprint "eagle-import:TO92-CBE")
      (libsource (lib "eagle-import") (part "-NPN-TO92-CBEMPS2222A"))
    )
    (comp (ref "T77")
      (value "MPS2222A-NPN-TO92-CBE")
      (footprint "eagle-import:TO92-CBE")
      (libsource (lib "eagle-import") (part "-NPN-TO92-CBEMPS2222A"))
    )
    (comp (ref "T78")
      (value "MPS2222A-NPN-TO92-CBE")
      (footprint "eagle-import:TO92-CBE")
      (libsource (lib "eagle-import") (part "-NPN-TO92-CBEMPS2222A"))
    )
    (comp (ref "T79")
      (value "MPS2222A-NPN-TO92-CBE")
      (footprint "eagle-import:TO92-CBE")
      (libsource (lib "eagle-import") (part "-NPN-TO92-CBEMPS2222A"))
    )
    (comp (ref "T80")
      (value "MPS2222A-NPN-TO92-CBE")
      (footprint "eagle-import:TO92-CBE")
      (libsource (lib "eagle-import") (part "-NPN-TO92-CBEMPS2222A"))
    )
    (comp (ref "T81")
      (value "MPS2222A-NPN-TO92-CBE")
      (footprint "eagle-import:TO92-CBE")
      (libsource (lib "eagle-import") (part "-NPN-TO92-CBEMPS2222A"))
    )
    (comp (ref "T82")
      (value "MPS2222A-NPN-TO92-CBE")
      (footprint "eagle-import:TO92-CBE")
      (libsource (lib "eagle-import") (part "-NPN-TO92-CBEMPS2222A"))
    )
    (comp (ref "T83")
      (value "MPS2222A-NPN-TO92-CBE")
      (footprint "eagle-import:TO92-CBE")
      (libsource (lib "eagle-import") (part "-NPN-TO92-CBEMPS2222A"))
    )
    (comp (ref "T84")
      (value "MPS2222A-NPN-TO92-CBE")
      (footprint "eagle-import:TO92-CBE")
      (libsource (lib "eagle-import") (part "-NPN-TO92-CBEMPS2222A"))
    )
    (comp (ref "T85")
      (value "MPS2222A-NPN-TO92-CBE")
      (footprint "eagle-import:TO92-CBE")
      (libsource (lib "eagle-import") (part "-NPN-TO92-CBEMPS2222A"))
    )
    (comp (ref "T86")
      (value "MPS2222A-NPN-TO92-CBE")
      (footprint "eagle-import:TO92-CBE")
      (libsource (lib "eagle-import") (part "-NPN-TO92-CBEMPS2222A"))
    )
    (comp (ref "T87")
      (value "MPS2222A-NPN-TO92-CBE")
      (footprint "eagle-import:TO92-CBE")
      (libsource (lib "eagle-import") (part "-NPN-TO92-CBEMPS2222A"))
    )
    (comp (ref "T88")
      (value "MPS2222A-NPN-TO92-CBE")
      (footprint "eagle-import:TO92-CBE")
      (libsource (lib "eagle-import") (part "-NPN-TO92-CBEMPS2222A"))
    )
    (comp (ref "T89")
      (value "MPS2222A-NPN-TO92-CBE")
      (footprint "eagle-import:TO92-CBE")
      (libsource (lib "eagle-import") (part "-NPN-TO92-CBEMPS2222A"))
    )
    (comp (ref "TAD")
      (value "BULB")
      (footprint "eagle-import:BULB")
      (libsource (lib "eagle-import") (part "BULB"))
    )
    (comp (ref "WORDCOUNT")
      (value "BULB")
      (footprint "eagle-import:BULB")
      (libsource (lib "eagle-import") (part "BULB"))
    )
  )
  (nets
    (net (code "1") (name "+15V") (class "Default")
      (node (ref "+V1") (pin "1") (pinfunction "1_1") (pintype "passive"))
      (node (ref "+V2") (pin "1") (pinfunction "1_1") (pintype "passive"))
      (node (ref "+V3") (pin "1") (pinfunction "1_1") (pintype "passive"))
      (node (ref "+V4") (pin "1") (pinfunction "1_1") (pintype "passive"))
      (node (ref "R1") (pin "1") (pinfunction "1_1") (pintype "passive"))
      (node (ref "R10") (pin "1") (pinfunction "1_1") (pintype "passive"))
      (node (ref "R11") (pin "1") (pinfunction "1_1") (pintype "passive"))
      (node (ref "R12") (pin "1") (pinfunction "1_1") (pintype "passive"))
      (node (ref "R13") (pin "1") (pinfunction "1_1") (pintype "passive"))
      (node (ref "R14") (pin "1") (pinfunction "1_1") (pintype "passive"))
      (node (ref "R15") (pin "1") (pinfunction "1_1") (pintype "passive"))
      (node (ref "R16") (pin "1") (pinfunction "1_1") (pintype "passive"))
      (node (ref "R17") (pin "1") (pinfunction "1_1") (pintype "passive"))
      (node (ref "R18") (pin "1") (pinfunction "1_1") (pintype "passive"))
      (node (ref "R19") (pin "1") (pinfunction "1_1") (pintype "passive"))
      (node (ref "R2") (pin "1") (pinfunction "1_1") (pintype "passive"))
      (node (ref "R20") (pin "1") (pinfunction "1_1") (pintype "passive"))
      (node (ref "R21") (pin "1") (pinfunction "1_1") (pintype "passive"))
      (node (ref "R22") (pin "1") (pinfunction "1_1") (pintype "passive"))
      (node (ref "R23") (pin "1") (pinfunction "1_1") (pintype "passive"))
      (node (ref "R24") (pin "1") (pinfunction "1_1") (pintype "passive"))
      (node (ref "R25") (pin "1") (pinfunction "1_1") (pintype "passive"))
      (node (ref "R26") (pin "1") (pinfunction "1_1") (pintype "passive"))
      (node (ref "R27") (pin "1") (pinfunction "1_1") (pintype "passive"))
      (node (ref "R28") (pin "1") (pinfunction "1_1") (pintype "passive"))
      (node (ref "R29") (pin "1") (pinfunction "1_1") (pintype "passive"))
      (node (ref "R3") (pin "1") (pinfunction "1_1") (pintype "passive"))
      (node (ref "R30") (pin "1") (pinfunction "1_1") (pintype "passive"))
      (node (ref "R31") (pin "1") (pinfunction "1_1") (pintype "passive"))
      (node (ref "R32") (pin "1") (pinfunction "1_1") (pintype "passive"))
      (node (ref "R33") (pin "1") (pinfunction "1_1") (pintype "passive"))
      (node (ref "R34") (pin "1") (pinfunction "1_1") (pintype "passive"))
      (node (ref "R35") (pin "1") (pinfunction "1_1") (pintype "passive"))
      (node (ref "R36") (pin "1") (pinfunction "1_1") (pintype "passive"))
      (node (ref "R37") (pin "1") (pinfunction "1_1") (pintype "passive"))
      (node (ref "R38") (pin "1") (pinfunction "1_1") (pintype "passive"))
      (node (ref "R39") (pin "1") (pinfunction "1_1") (pintype "passive"))
      (node (ref "R4") (pin "1") (pinfunction "1_1") (pintype "passive"))
      (node (ref "R40") (pin "1") (pinfunction "1_1") (pintype "passive"))
      (node (ref "R41") (pin "1") (pinfunction "1_1") (pintype "passive"))
      (node (ref "R42") (pin "1") (pinfunction "1_1") (pintype "passive"))
      (node (ref "R43") (pin "1") (pinfunction "1_1") (pintype "passive"))
      (node (ref "R44") (pin "1") (pinfunction "1_1") (pintype "passive"))
      (node (ref "R45") (pin "1") (pinfunction "1_1") (pintype "passive"))
      (node (ref "R46") (pin "1") (pinfunction "1_1") (pintype "passive"))
      (node (ref "R47") (pin "1") (pinfunction "1_1") (pintype "passive"))
      (node (ref "R48") (pin "1") (pinfunction "1_1") (pintype "passive"))
      (node (ref "R49") (pin "1") (pinfunction "1_1") (pintype "passive"))
      (node (ref "R5") (pin "1") (pinfunction "1_1") (pintype "passive"))
      (node (ref "R50") (pin "1") (pinfunction "1_1") (pintype "passive"))
      (node (ref "R51") (pin "1") (pinfunction "1_1") (pintype "passive"))
      (node (ref "R52") (pin "1") (pinfunction "1_1") (pintype "passive"))
      (node (ref "R53") (pin "1") (pinfunction "1_1") (pintype "passive"))
      (node (ref "R54") (pin "1") (pinfunction "1_1") (pintype "passive"))
      (node (ref "R55") (pin "1") (pinfunction "1_1") (pintype "passive"))
      (node (ref "R56") (pin "1") (pinfunction "1_1") (pintype "passive"))
      (node (ref "R57") (pin "1") (pinfunction "1_1") (pintype "passive"))
      (node (ref "R58") (pin "1") (pinfunction "1_1") (pintype "passive"))
      (node (ref "R59") (pin "1") (pinfunction "1_1") (pintype "passive"))
      (node (ref "R6") (pin "1") (pinfunction "1_1") (pintype "passive"))
      (node (ref "R60") (pin "1") (pinfunction "1_1") (pintype "passive"))
      (node (ref "R61") (pin "1") (pinfunction "1_1") (pintype "passive"))
      (node (ref "R62") (pin "1") (pinfunction "1_1") (pintype "passive"))
      (node (ref "R63") (pin "1") (pinfunction "1_1") (pintype "passive"))
      (node (ref "R64") (pin "1") (pinfunction "1_1") (pintype "passive"))
      (node (ref "R65") (pin "1") (pinfunction "1_1") (pintype "passive"))
      (node (ref "R66") (pin "1") (pinfunction "1_1") (pintype "passive"))
      (node (ref "R67") (pin "1") (pinfunction "1_1") (pintype "passive"))
      (node (ref "R68") (pin "1") (pinfunction "1_1") (pintype "passive"))
      (node (ref "R69") (pin "1") (pinfunction "1_1") (pintype "passive"))
      (node (ref "R7") (pin "1") (pinfunction "1_1") (pintype "passive"))
      (node (ref "R70") (pin "1") (pinfunction "1_1") (pintype "passive"))
      (node (ref "R71") (pin "1") (pinfunction "1_1") (pintype "passive"))
      (node (ref "R72") (pin "1") (pinfunction "1_1") (pintype "passive"))
      (node (ref "R73") (pin "1") (pinfunction "1_1") (pintype "passive"))
      (node (ref "R74") (pin "1") (pinfunction "1_1") (pintype "passive"))
      (node (ref "R75") (pin "1") (pinfunction "1_1") (pintype "passive"))
      (node (ref "R76") (pin "1") (pinfunction "1_1") (pintype "passive"))
      (node (ref "R77") (pin "1") (pinfunction "1_1") (pintype "passive"))
      (node (ref "R78") (pin "1") (pinfunction "1_1") (pintype "passive"))
      (node (ref "R79") (pin "1") (pinfunction "1_1") (pintype "passive"))
      (node (ref "R8") (pin "1") (pinfunction "1_1") (pintype "passive"))
      (node (ref "R80") (pin "1") (pinfunction "1_1") (pintype "passive"))
      (node (ref "R81") (pin "1") (pinfunction "1_1") (pintype "passive"))
      (node (ref "R82") (pin "1") (pinfunction "1_1") (pintype "passive"))
      (node (ref "R83") (pin "1") (pinfunction "1_1") (pintype "passive"))
      (node (ref "R84") (pin "1") (pinfunction "1_1") (pintype "passive"))
      (node (ref "R85") (pin "1") (pinfunction "1_1") (pintype "passive"))
      (node (ref "R86") (pin "1") (pinfunction "1_1") (pintype "passive"))
      (node (ref "R87") (pin "1") (pinfunction "1_1") (pintype "passive"))
      (node (ref "R88") (pin "1") (pinfunction "1_1") (pintype "passive"))
      (node (ref "R89") (pin "1") (pinfunction "1_1") (pintype "passive"))
      (node (ref "R9") (pin "1") (pinfunction "1_1") (pintype "passive"))
    )
    (net (code "2") (name "AC0") (class "Default")
      (node (ref "D40TOP") (pin "4") (pinfunction "1_4") (pintype "passive"))
      (node (ref "E40") (pin "7") (pinfunction "7_7") (pintype "passive"))
      (node (ref "T43") (pin "B") (pinfunction "B_B") (pintype "passive"))
    )
    (net (code "3") (name "AC1") (class "Default")
      (node (ref "D40BOT") (pin "2") (pinfunction "1_2") (pintype "passive"))
      (node (ref "E40") (pin "4") (pinfunction "4_4") (pintype "passive"))
      (node (ref "T44") (pin "B") (pinfunction "B_B") (pintype "passive"))
    )
    (net (code "4") (name "AC2") (class "Default")
      (node (ref "D40TOP") (pin "12") (pinfunction "1_12") (pintype "passive"))
      (node (ref "E40") (pin "21") (pinfunction "21_21") (pintype "passive"))
      (node (ref "T45") (pin "B") (pinfunction "B_B") (pintype "passive"))
    )
    (net (code "5") (name "AC3") (class "Default")
      (node (ref "D40BOT") (pin "9") (pinfunction "1_9") (pintype "passive"))
      (node (ref "E40") (pin "14") (pinfunction "14_14") (pintype "passive"))
      (node (ref "T46") (pin "B") (pinfunction "B_B") (pintype "passive"))
    )
    (net (code "6") (name "AC4") (class "Default")
      (node (ref "D40TOP") (pin "17") (pinfunction "1_17") (pintype "passive"))
      (node (ref "E40") (pin "31") (pinfunction "31_31") (pintype "passive"))
      (node (ref "T47") (pin "B") (pinfunction "B_B") (pintype "passive"))
    )
    (net (code "7") (name "AC5") (class "Default")
      (node (ref "D40BOT") (pin "16") (pinfunction "1_16") (pintype "passive"))
      (node (ref "E40") (pin "28") (pinfunction "28_28") (pintype "passive"))
      (node (ref "T48") (pin "B") (pinfunction "B_B") (pintype "passive"))
    )
    (net (code "8") (name "AC6") (class "Default")
      (node (ref "E40TOP") (pin "4") (pinfunction "1_4") (pintype "passive"))
      (node (ref "F40") (pin "7") (pinfunction "7_7") (pintype "passive"))
      (node (ref "T49") (pin "B") (pinfunction "B_B") (pintype "passive"))
    )
    (net (code "9") (name "AC7") (class "Default")
      (node (ref "E40BOT") (pin "2") (pinfunction "1_2") (pintype "passive"))
      (node (ref "F40") (pin "4") (pinfunction "4_4") (pintype "passive"))
      (node (ref "T50") (pin "B") (pinfunction "B_B") (pintype "passive"))
    )
    (net (code "10") (name "AC8") (class "Default")
      (node (ref "E40TOP") (pin "12") (pinfunction "1_12") (pintype "passive"))
      (node (ref "F40") (pin "21") (pinfunction "21_21") (pintype "passive"))
      (node (ref "T51") (pin "B") (pinfunction "B_B") (pintype "passive"))
    )
    (net (code "11") (name "AC9") (class "Default")
      (node (ref "E40BOT") (pin "9") (pinfunction "1_9") (pintype "passive"))
      (node (ref "F40") (pin "14") (pinfunction "14_14") (pintype "passive"))
      (node (ref "T52") (pin "B") (pinfunction "B_B") (pintype "passive"))
    )
    (net (code "12") (name "AC10") (class "Default")
      (node (ref "E40TOP") (pin "17") (pinfunction "1_17") (pintype "passive"))
      (node (ref "F40") (pin "31") (pinfunction "31_31") (pintype "passive"))
      (node (ref "T53") (pin "B") (pinfunction "B_B") (pintype "passive"))
    )
    (net (code "13") (name "AC11") (class "Default")
      (node (ref "E40BOT") (pin "16") (pinfunction "1_16") (pintype "passive"))
      (node (ref "F40") (pin "28") (pinfunction "28_28") (pintype "passive"))
      (node (ref "T54") (pin "B") (pinfunction "B_B") (pintype "passive"))
    )
    (net (code "14") (name "AND") (class "Default")
      (node (ref "D40") (pin "2") (pinfunction "2_2") (pintype "passive"))
      (node (ref "F40BOT") (pin "1") (pinfunction "1_1") (pintype "passive"))
      (node (ref "T82") (pin "B") (pinfunction "B_B") (pintype "passive"))
    )
    (net (code "15") (name "BREAK") (class "Default")
      (node (ref "D40") (pin "22") (pinfunction "22_22") (pintype "passive"))
      (node (ref "F40BOT") (pin "12") (pinfunction "1_12") (pintype "passive"))
      (node (ref "T81") (pin "B") (pinfunction "B_B") (pintype "passive"))
    )
    (net (code "16") (name "CA") (class "Default")
      (node (ref "D40") (pin "32") (pinfunction "32_32") (pintype "passive"))
      (node (ref "F40BOT") (pin "18") (pinfunction "1_18") (pintype "passive"))
      (node (ref "T80") (pin "B") (pinfunction "B_B") (pintype "passive"))
    )
    (net (code "17") (name "DCA") (class "Default")
      (node (ref "D40") (pin "8") (pinfunction "8_8") (pintype "passive"))
      (node (ref "F40BOT") (pin "4") (pinfunction "1_4") (pintype "passive"))
      (node (ref "T85") (pin "B") (pinfunction "B_B") (pintype "passive"))
    )
    (net (code "18") (name "DEFER") (class "Default")
      (node (ref "D40") (pin "28") (pinfunction "28_28") (pintype "passive"))
      (node (ref "F40BOT") (pin "16") (pinfunction "1_16") (pintype "passive"))
      (node (ref "T78") (pin "B") (pinfunction "B_B") (pintype "passive"))
    )
    (net (code "19") (name "DF0") (class "Default")
      (node (ref "C40") (pin "1") (pinfunction "1_1") (pintype "passive"))
      (node (ref "C40TOP") (pin "1") (pinfunction "1_1") (pintype "passive"))
      (node (ref "T1") (pin "B") (pinfunction "B_B") (pintype "passive"))
    )
    (net (code "20") (name "DF1") (class "Default")
      (node (ref "C40") (pin "10") (pinfunction "10_10") (pintype "passive"))
      (node (ref "C40BOT") (pin "5") (pinfunction "1_5") (pintype "passive"))
      (node (ref "T2") (pin "B") (pinfunction "B_B") (pintype "passive"))
    )
    (net (code "21") (name "DF2") (class "Default")
      (node (ref "C40") (pin "11") (pinfunction "11_11") (pintype "passive"))
      (node (ref "C40TOP") (pin "6") (pinfunction "1_6") (pintype "passive"))
      (node (ref "T3") (pin "B") (pinfunction "B_B") (pintype "passive"))
    )
    (net (code "22") (name "EXECUTE") (class "Default")
      (node (ref "D40") (pin "26") (pinfunction "26_26") (pintype "passive"))
      (node (ref "F40BOT") (pin "15") (pinfunction "1_15") (pintype "passive"))
      (node (ref "T77") (pin "B") (pinfunction "B_B") (pintype "passive"))
    )
    (net (code "23") (name "FETCH") (class "Default")
      (node (ref "D40") (pin "24") (pinfunction "24_24") (pintype "passive"))
      (node (ref "F40BOT") (pin "14") (pinfunction "1_14") (pintype "passive"))
      (node (ref "T76") (pin "B") (pinfunction "B_B") (pintype "passive"))
    )
    (net (code "24") (name "GND") (class "Default")
      (node (ref "C40") (pin "17") (pinfunction "17_17") (pintype "passive"))
      (node (ref "C40") (pin "18") (pinfunction "18_18") (pintype "passive"))
      (node (ref "C40") (pin "19") (pinfunction "19_19") (pintype "passive"))
      (node (ref "C40") (pin "20") (pinfunction "20_20") (pintype "passive"))
      (node (ref "C40BOT") (pin "13") (pinfunction "1_13") (pintype "passive"))
      (node (ref "D40") (pin "17") (pinfunction "17_17") (pintype "passive"))
      (node (ref "D40") (pin "18") (pinfunction "18_18") (pintype "passive"))
      (node (ref "D40") (pin "19") (pinfunction "19_19") (pintype "passive"))
      (node (ref "D40") (pin "20") (pinfunction "20_20") (pintype "passive"))
      (node (ref "D40BOT") (pin "13") (pinfunction "1_13") (pintype "passive"))
      (node (ref "E40") (pin "17") (pinfunction "17_17") (pintype "passive"))
      (node (ref "E40") (pin "18") (pinfunction "18_18") (pintype "passive"))
      (node (ref "E40") (pin "19") (pinfunction "19_19") (pintype "passive"))
      (node (ref "E40") (pin "20") (pinfunction "20_20") (pintype "passive"))
      (node (ref "E40BOT") (pin "13") (pinfunction "1_13") (pintype "passive"))
      (node (ref "F40") (pin "17") (pinfunction "17_17") (pintype "passive"))
      (node (ref "F40") (pin "18") (pinfunction "18_18") (pintype "passive"))
      (node (ref "F40") (pin "19") (pinfunction "19_19") (pintype "passive"))
      (node (ref "F40") (pin "20") (pinfunction "20_20") (pintype "passive"))
      (node (ref "F40BOT") (pin "13") (pinfunction "1_13") (pintype "passive"))
      (node (ref "GND1") (pin "1") (pinfunction "1_1") (pintype "passive"))
      (node (ref "GND2") (pin "1") (pinfunction "1_1") (pintype "passive"))
      (node (ref "GND3") (pin "1") (pinfunction "1_1") (pintype "passive"))
      (node (ref "GND4") (pin "1") (pinfunction "1_1") (pintype "passive"))
      (node (ref "T1") (pin "E") (pinfunction "E_E") (pintype "passive"))
      (node (ref "T10") (pin "E") (pinfunction "E_E") (pintype "passive"))
      (node (ref "T11") (pin "E") (pinfunction "E_E") (pintype "passive"))
      (node (ref "T12") (pin "E") (pinfunction "E_E") (pintype "passive"))
      (node (ref "T13") (pin "E") (pinfunction "E_E") (pintype "passive"))
      (node (ref "T14") (pin "E") (pinfunction "E_E") (pintype "passive"))
      (node (ref "T15") (pin "E") (pinfunction "E_E") (pintype "passive"))
      (node (ref "T16") (pin "E") (pinfunction "E_E") (pintype "passive"))
      (node (ref "T17") (pin "E") (pinfunction "E_E") (pintype "passive"))
      (node (ref "T18") (pin "E") (pinfunction "E_E") (pintype "passive"))
      (node (ref "T19") (pin "E") (pinfunction "E_E") (pintype "passive"))
      (node (ref "T2") (pin "E") (pinfunction "E_E") (pintype "passive"))
      (node (ref "T20") (pin "E") (pinfunction "E_E") (pintype "passive"))
      (node (ref "T21") (pin "E") (pinfunction "E_E") (pintype "passive"))
      (node (ref "T22") (pin "E") (pinfunction "E_E") (pintype "passive"))
      (node (ref "T23") (pin "E") (pinfunction "E_E") (pintype "passive"))
      (node (ref "T24") (pin "E") (pinfunction "E_E") (pintype "passive"))
      (node (ref "T25") (pin "E") (pinfunction "E_E") (pintype "passive"))
      (node (ref "T26") (pin "E") (pinfunction "E_E") (pintype "passive"))
      (node (ref "T27") (pin "E") (pinfunction "E_E") (pintype "passive"))
      (node (ref "T28") (pin "E") (pinfunction "E_E") (pintype "passive"))
      (node (ref "T29") (pin "E") (pinfunction "E_E") (pintype "passive"))
      (node (ref "T3") (pin "E") (pinfunction "E_E") (pintype "passive"))
      (node (ref "T30") (pin "E") (pinfunction "E_E") (pintype "passive"))
      (node (ref "T31") (pin "E") (pinfunction "E_E") (pintype "passive"))
      (node (ref "T32") (pin "E") (pinfunction "E_E") (pintype "passive"))
      (node (ref "T33") (pin "E") (pinfunction "E_E") (pintype "passive"))
      (node (ref "T34") (pin "E") (pinfunction "E_E") (pintype "passive"))
      (node (ref "T35") (pin "E") (pinfunction "E_E") (pintype "passive"))
      (node (ref "T36") (pin "E") (pinfunction "E_E") (pintype "passive"))
      (node (ref "T37") (pin "E") (pinfunction "E_E") (pintype "passive"))
      (node (ref "T38") (pin "E") (pinfunction "E_E") (pintype "passive"))
      (node (ref "T39") (pin "E") (pinfunction "E_E") (pintype "passive"))
      (node (ref "T4") (pin "E") (pinfunction "E_E") (pintype "passive"))
      (node (ref "T40") (pin "E") (pinfunction "E_E") (pintype "passive"))
      (node (ref "T41") (pin "E") (pinfunction "E_E") (pintype "passive"))
      (node (ref "T42") (pin "E") (pinfunction "E_E") (pintype "passive"))
      (node (ref "T43") (pin "E") (pinfunction "E_E") (pintype "passive"))
      (node (ref "T44") (pin "E") (pinfunction "E_E") (pintype "passive"))
      (node (ref "T45") (pin "E") (pinfunction "E_E") (pintype "passive"))
      (node (ref "T46") (pin "E") (pinfunction "E_E") (pintype "passive"))
      (node (ref "T47") (pin "E") (pinfunction "E_E") (pintype "passive"))
      (node (ref "T48") (pin "E") (pinfunction "E_E") (pintype "passive"))
      (node (ref "T49") (pin "E") (pinfunction "E_E") (pintype "passive"))
      (node (ref "T5") (pin "E") (pinfunction "E_E") (pintype "passive"))
      (node (ref "T50") (pin "E") (pinfunction "E_E") (pintype "passive"))
      (node (ref "T51") (pin "E") (pinfunction "E_E") (pintype "passive"))
      (node (ref "T52") (pin "E") (pinfunction "E_E") (pintype "passive"))
      (node (ref "T53") (pin "E") (pinfunction "E_E") (pintype "passive"))
      (node (ref "T54") (pin "E") (pinfunction "E_E") (pintype "passive"))
      (node (ref "T55") (pin "E") (pinfunction "E_E") (pintype "passive"))
      (node (ref "T56") (pin "E") (pinfunction "E_E") (pintype "passive"))
      (node (ref "T57") (pin "E") (pinfunction "E_E") (pintype "passive"))
      (node (ref "T58") (pin "E") (pinfunction "E_E") (pintype "passive"))
      (node (ref "T59") (pin "E") (pinfunction "E_E") (pintype "passive"))
      (node (ref "T6") (pin "E") (pinfunction "E_E") (pintype "passive"))
      (node (ref "T60") (pin "E") (pinfunction "E_E") (pintype "passive"))
      (node (ref "T61") (pin "E") (pinfunction "E_E") (pintype "passive"))
      (node (ref "T62") (pin "E") (pinfunction "E_E") (pintype "passive"))
      (node (ref "T63") (pin "E") (pinfunction "E_E") (pintype "passive"))
      (node (ref "T64") (pin "E") (pinfunction "E_E") (pintype "passive"))
      (node (ref "T65") (pin "E") (pinfunction "E_E") (pintype "passive"))
      (node (ref "T66") (pin "E") (pinfunction "E_E") (pintype "passive"))
      (node (ref "T67") (pin "E") (pinfunction "E_E") (pintype "passive"))
      (node (ref "T68") (pin "E") (pinfunction "E_E") (pintype "passive"))
      (node (ref "T69") (pin "E") (pinfunction "E_E") (pintype "passive"))
      (node (ref "T7") (pin "E") (pinfunction "E_E") (pintype "passive"))
      (node (ref "T70") (pin "E") (pinfunction "E_E") (pintype "passive"))
      (node (ref "T71") (pin "E") (pinfunction "E_E") (pintype "passive"))
      (node (ref "T72") (pin "E") (pinfunction "E_E") (pintype "passive"))
      (node (ref "T73") (pin "E") (pinfunction "E_E") (pintype "passive"))
      (node (ref "T74") (pin "E") (pinfunction "E_E") (pintype "passive"))
      (node (ref "T75") (pin "E") (pinfunction "E_E") (pintype "passive"))
      (node (ref "T76") (pin "E") (pinfunction "E_E") (pintype "passive"))
      (node (ref "T77") (pin "E") (pinfunction "E_E") (pintype "passive"))
      (node (ref "T78") (pin "E") (pinfunction "E_E") (pintype "passive"))
      (node (ref "T79") (pin "E") (pinfunction "E_E") (pintype "passive"))
      (node (ref "T8") (pin "E") (pinfunction "E_E") (pintype "passive"))
      (node (ref "T80") (pin "E") (pinfunction "E_E") (pintype "passive"))
      (node (ref "T81") (pin "E") (pinfunction "E_E") (pintype "passive"))
      (node (ref "T82") (pin "E") (pinfunction "E_E") (pintype "passive"))
      (node (ref "T83") (pin "E") (pinfunction "E_E") (pintype "passive"))
      (node (ref "T84") (pin "E") (pinfunction "E_E") (pintype "passive"))
      (node (ref "T85") (pin "E") (pinfunction "E_E") (pintype "passive"))
      (node (ref "T86") (pin "E") (pinfunction "E_E") (pintype "passive"))
      (node (ref "T87") (pin "E") (pinfunction "E_E") (pintype "passive"))
      (node (ref "T88") (pin "E") (pinfunction "E_E") (pintype "passive"))
      (node (ref "T89") (pin "E") (pinfunction "E_E") (pintype "passive"))
      (node (ref "T9") (pin "E") (pinfunction "E_E") (pintype "passive"))
    )
    (net (code "25") (name "IF0") (class "Default")
      (node (ref "C40") (pin "24") (pinfunction "24_24") (pintype "passive"))
      (node (ref "C40BOT") (pin "14") (pinfunction "1_14") (pintype "passive"))
      (node (ref "T4") (pin "B") (pinfunction "B_B") (pintype "passive"))
    )
    (net (code "26") (name "IF1") (class "Default")
      (node (ref "C40") (pin "25") (pinfunction "25_25") (pintype "passive"))
      (node (ref "C40TOP") (pin "14") (pinfunction "1_14") (pintype "passive"))
      (node (ref "T5") (pin "B") (pinfunction "B_B") (pintype "passive"))
    )
    (net (code "27") (name "IF2") (class "Default")
      (node (ref "C40") (pin "34") (pinfunction "34_34") (pintype "passive"))
      (node (ref "C40BOT") (pin "19") (pinfunction "1_19") (pintype "passive"))
      (node (ref "T6") (pin "B") (pinfunction "B_B") (pintype "passive"))
    )
    (net (code "28") (name "ION") (class "Default")
      (node (ref "D40") (pin "34") (pinfunction "34_34") (pintype "passive"))
      (node (ref "F40BOT") (pin "19") (pinfunction "1_19") (pintype "passive"))
      (node (ref "T73") (pin "B") (pinfunction "B_B") (pintype "passive"))
    )
    (net (code "29") (name "IOT") (class "Default")
      (node (ref "D40") (pin "14") (pinfunction "14_14") (pintype "passive"))
      (node (ref "F40BOT") (pin "9") (pinfunction "1_9") (pintype "passive"))
      (node (ref "T88") (pin "B") (pinfunction "B_B") (pintype "passive"))
    )
    (net (code "30") (name "ISZ") (class "Default")
      (node (ref "D40") (pin "6") (pinfunction "6_6") (pintype "passive"))
      (node (ref "F40BOT") (pin "3") (pinfunction "1_3") (pintype "passive"))
      (node (ref "T84") (pin "B") (pinfunction "B_B") (pintype "passive"))
    )
    (net (code "31") (name "JMP") (class "Default")
      (node (ref "D40") (pin "12") (pinfunction "12_12") (pintype "passive"))
      (node (ref "F40BOT") (pin "6") (pinfunction "1_6") (pintype "passive"))
      (node (ref "T87") (pin "B") (pinfunction "B_B") (pintype "passive"))
    )
    (net (code "32") (name "JMS") (class "Default")
      (node (ref "D40") (pin "10") (pinfunction "10_10") (pintype "passive"))
      (node (ref "F40BOT") (pin "5") (pinfunction "1_5") (pintype "passive"))
      (node (ref "T86") (pin "B") (pinfunction "B_B") (pintype "passive"))
    )
    (net (code "33") (name "LINK") (class "Default")
      (node (ref "C40") (pin "28") (pinfunction "28_28") (pintype "passive"))
      (node (ref "C40BOT") (pin "16") (pinfunction "1_16") (pintype "passive"))
      (node (ref "T72") (pin "B") (pinfunction "B_B") (pintype "passive"))
    )
    (net (code "34") (name "MA0") (class "Default")
      (node (ref "D40TOP") (pin "2") (pinfunction "1_2") (pintype "passive"))
      (node (ref "E40") (pin "3") (pinfunction "3_3") (pintype "passive"))
      (node (ref "T19") (pin "B") (pinfunction "B_B") (pintype "passive"))
    )
    (net (code "35") (name "MA1") (class "Default")
      (node (ref "D40BOT") (pin "4") (pinfunction "1_4") (pintype "passive"))
      (node (ref "E40") (pin "8") (pinfunction "8_8") (pintype "passive"))
      (node (ref "T20") (pin "B") (pinfunction "B_B") (pintype "passive"))
    )
    (net (code "36") (name "MA2") (class "Default")
      (node (ref "D40TOP") (pin "7") (pinfunction "1_7") (pintype "passive"))
      (node (ref "E40") (pin "13") (pinfunction "13_13") (pintype "passive"))
      (node (ref "T21") (pin "B") (pinfunction "B_B") (pintype "passive"))
    )
    (net (code "37") (name "MA3") (class "Default")
      (node (ref "D40BOT") (pin "12") (pinfunction "1_12") (pintype "passive"))
      (node (ref "E40") (pin "22") (pinfunction "22_22") (pintype "passive"))
      (node (ref "T22") (pin "B") (pinfunction "B_B") (pintype "passive"))
    )
    (net (code "38") (name "MA4") (class "Default")
      (node (ref "D40TOP") (pin "15") (pinfunction "1_15") (pintype "passive"))
      (node (ref "E40") (pin "27") (pinfunction "27_27") (pintype "passive"))
      (node (ref "T23") (pin "B") (pinfunction "B_B") (pintype "passive"))
    )
    (net (code "39") (name "MA5") (class "Default")
      (node (ref "D40BOT") (pin "18") (pinfunction "1_18") (pintype "passive"))
      (node (ref "E40") (pin "32") (pinfunction "32_32") (pintype "passive"))
      (node (ref "T24") (pin "B") (pinfunction "B_B") (pintype "passive"))
    )
    (net (code "40") (name "MA6") (class "Default")
      (node (ref "E40TOP") (pin "2") (pinfunction "1_2") (pintype "passive"))
      (node (ref "F40") (pin "3") (pinfunction "3_3") (pintype "passive"))
      (node (ref "T25") (pin "B") (pinfunction "B_B") (pintype "passive"))
    )
    (net (code "41") (name "MA7") (class "Default")
      (node (ref "E40BOT") (pin "4") (pinfunction "1_4") (pintype "passive"))
      (node (ref "F40") (pin "8") (pinfunction "8_8") (pintype "passive"))
      (node (ref "T26") (pin "B") (pinfunction "B_B") (pintype "passive"))
    )
    (net (code "42") (name "MA8") (class "Default")
      (node (ref "E40TOP") (pin "7") (pinfunction "1_7") (pintype "passive"))
      (node (ref "F40") (pin "13") (pinfunction "13_13") (pintype "passive"))
      (node (ref "T27") (pin "B") (pinfunction "B_B") (pintype "passive"))
    )
    (net (code "43") (name "MA9") (class "Default")
      (node (ref "E40BOT") (pin "12") (pinfunction "1_12") (pintype "passive"))
      (node (ref "F40") (pin "22") (pinfunction "22_22") (pintype "passive"))
      (node (ref "T28") (pin "B") (pinfunction "B_B") (pintype "passive"))
    )
    (net (code "44") (name "MA10") (class "Default")
      (node (ref "E40TOP") (pin "15") (pinfunction "1_15") (pintype "passive"))
      (node (ref "F40") (pin "27") (pinfunction "27_27") (pintype "passive"))
      (node (ref "T29") (pin "B") (pinfunction "B_B") (pintype "passive"))
    )
    (net (code "45") (name "MA11") (class "Default")
      (node (ref "E40BOT") (pin "18") (pinfunction "1_18") (pintype "passive"))
      (node (ref "F40") (pin "32") (pinfunction "32_32") (pintype "passive"))
      (node (ref "T30") (pin "B") (pinfunction "B_B") (pintype "passive"))
    )
    (net (code "46") (name "MB0") (class "Default")
      (node (ref "D40TOP") (pin "3") (pinfunction "1_3") (pintype "passive"))
      (node (ref "E40") (pin "5") (pinfunction "5_5") (pintype "passive"))
      (node (ref "T31") (pin "B") (pinfunction "B_B") (pintype "passive"))
    )
    (net (code "47") (name "MB1") (class "Default")
      (node (ref "D40BOT") (pin "3") (pinfunction "1_3") (pintype "passive"))
      (node (ref "E40") (pin "6") (pinfunction "6_6") (pintype "passive"))
      (node (ref "T32") (pin "B") (pinfunction "B_B") (pintype "passive"))
    )
    (net (code "48") (name "MB2") (class "Default")
      (node (ref "D40TOP") (pin "8") (pinfunction "1_8") (pintype "passive"))
      (node (ref "E40") (pin "15") (pinfunction "15_15") (pintype "passive"))
      (node (ref "T33") (pin "B") (pinfunction "B_B") (pintype "passive"))
    )
    (net (code "49") (name "MB3") (class "Default")
      (node (ref "D40BOT") (pin "11") (pinfunction "1_11") (pintype "passive"))
      (node (ref "E40") (pin "16") (pinfunction "16_16") (pintype "passive"))
      (node (ref "T34") (pin "B") (pinfunction "B_B") (pintype "passive"))
    )
    (net (code "50") (name "MB4") (class "Default")
      (node (ref "D40TOP") (pin "16") (pinfunction "1_16") (pintype "passive"))
      (node (ref "E40") (pin "29") (pinfunction "29_29") (pintype "passive"))
      (node (ref "T35") (pin "B") (pinfunction "B_B") (pintype "passive"))
    )
    (net (code "51") (name "MB5") (class "Default")
      (node (ref "D40BOT") (pin "17") (pinfunction "1_17") (pintype "passive"))
      (node (ref "E40") (pin "30") (pinfunction "30_30") (pintype "passive"))
      (node (ref "T36") (pin "B") (pinfunction "B_B") (pintype "passive"))
    )
    (net (code "52") (name "MB6") (class "Default")
      (node (ref "E40TOP") (pin "3") (pinfunction "1_3") (pintype "passive"))
      (node (ref "F40") (pin "5") (pinfunction "5_5") (pintype "passive"))
      (node (ref "T37") (pin "B") (pinfunction "B_B") (pintype "passive"))
    )
    (net (code "53") (name "MB7") (class "Default")
      (node (ref "E40BOT") (pin "3") (pinfunction "1_3") (pintype "passive"))
      (node (ref "F40") (pin "6") (pinfunction "6_6") (pintype "passive"))
      (node (ref "T38") (pin "B") (pinfunction "B_B") (pintype "passive"))
    )
    (net (code "54") (name "MB8") (class "Default")
      (node (ref "E40TOP") (pin "8") (pinfunction "1_8") (pintype "passive"))
      (node (ref "F40") (pin "15") (pinfunction "15_15") (pintype "passive"))
      (node (ref "T39") (pin "B") (pinfunction "B_B") (pintype "passive"))
    )
    (net (code "55") (name "MB9") (class "Default")
      (node (ref "E40BOT") (pin "11") (pinfunction "1_11") (pintype "passive"))
      (node (ref "F40") (pin "16") (pinfunction "16_16") (pintype "passive"))
      (node (ref "T40") (pin "B") (pinfunction "B_B") (pintype "passive"))
    )
    (net (code "56") (name "MB10") (class "Default")
      (node (ref "E40TOP") (pin "16") (pinfunction "1_16") (pintype "passive"))
      (node (ref "F40") (pin "29") (pinfunction "29_29") (pintype "passive"))
      (node (ref "T41") (pin "B") (pinfunction "B_B") (pintype "passive"))
    )
    (net (code "57") (name "MB11") (class "Default")
      (node (ref "E40BOT") (pin "17") (pinfunction "1_17") (pintype "passive"))
      (node (ref "F40") (pin "30") (pinfunction "30_30") (pintype "passive"))
      (node (ref "T42") (pin "B") (pinfunction "B_B") (pintype "passive"))
    )
    (net (code "58") (name "MQ0") (class "Default")
      (node (ref "D40TOP") (pin "5") (pinfunction "1_5") (pintype "passive"))
      (node (ref "E40") (pin "9") (pinfunction "9_9") (pintype "passive"))
      (node (ref "T55") (pin "B") (pinfunction "B_B") (pintype "passive"))
    )
    (net (code "59") (name "MQ1") (class "Default")
      (node (ref "D40BOT") (pin "1") (pinfunction "1_1") (pintype "passive"))
      (node (ref "E40") (pin "2") (pinfunction "2_2") (pintype "passive"))
      (node (ref "T56") (pin "B") (pinfunction "B_B") (pintype "passive"))
    )
    (net (code "60") (name "MQ2") (class "Default")
      (node (ref "D40TOP") (pin "13") (pinfunction "1_13") (pintype "passive"))
      (node (ref "E40") (pin "23") (pinfunction "23_23") (pintype "passive"))
      (node (ref "T57") (pin "B") (pinfunction "B_B") (pintype "passive"))
    )
    (net (code "61") (name "MQ3") (class "Default")
      (node (ref "D40BOT") (pin "6") (pinfunction "1_6") (pintype "passive"))
      (node (ref "E40") (pin "12") (pinfunction "12_12") (pintype "passive"))
      (node (ref "T58") (pin "B") (pinfunction "B_B") (pintype "passive"))
    )
    (net (code "62") (name "MQ4") (class "Default")
      (node (ref "D40TOP") (pin "18") (pinfunction "1_18") (pintype "passive"))
      (node (ref "E40") (pin "33") (pinfunction "33_33") (pintype "passive"))
      (node (ref "T59") (pin "B") (pinfunction "B_B") (pintype "passive"))
    )
    (net (code "63") (name "MQ5") (class "Default")
      (node (ref "D40BOT") (pin "15") (pinfunction "1_15") (pintype "passive"))
      (node (ref "E40") (pin "26") (pinfunction "26_26") (pintype "passive"))
      (node (ref "T60") (pin "B") (pinfunction "B_B") (pintype "passive"))
    )
    (net (code "64") (name "MQ6") (class "Default")
      (node (ref "E40TOP") (pin "5") (pinfunction "1_5") (pintype "passive"))
      (node (ref "F40") (pin "9") (pinfunction "9_9") (pintype "passive"))
      (node (ref "T61") (pin "B") (pinfunction "B_B") (pintype "passive"))
    )
    (net (code "65") (name "MQ7") (class "Default")
      (node (ref "E40BOT") (pin "1") (pinfunction "1_1") (pintype "passive"))
      (node (ref "F40") (pin "2") (pinfunction "2_2") (pintype "passive"))
      (node (ref "T62") (pin "B") (pinfunction "B_B") (pintype "passive"))
    )
    (net (code "66") (name "MQ8") (class "Default")
      (node (ref "E40TOP") (pin "13") (pinfunction "1_13") (pintype "passive"))
      (node (ref "F40") (pin "23") (pinfunction "23_23") (pintype "passive"))
      (node (ref "T63") (pin "B") (pinfunction "B_B") (pintype "passive"))
    )
    (net (code "67") (name "MQ9") (class "Default")
      (node (ref "E40BOT") (pin "6") (pinfunction "1_6") (pintype "passive"))
      (node (ref "F40") (pin "12") (pinfunction "12_12") (pintype "passive"))
      (node (ref "T64") (pin "B") (pinfunction "B_B") (pintype "passive"))
    )
    (net (code "68") (name "MQ10") (class "Default")
      (node (ref "E40TOP") (pin "18") (pinfunction "1_18") (pintype "passive"))
      (node (ref "F40") (pin "33") (pinfunction "33_33") (pintype "passive"))
      (node (ref "T65") (pin "B") (pinfunction "B_B") (pintype "passive"))
    )
    (net (code "69") (name "MQ11") (class "Default")
      (node (ref "E40BOT") (pin "15") (pinfunction "1_15") (pintype "passive"))
      (node (ref "F40") (pin "26") (pinfunction "26_26") (pintype "passive"))
      (node (ref "T66") (pin "B") (pinfunction "B_B") (pintype "passive"))
    )
    (net (code "70") (name "Net-(AC0-PadA)") (class "Default")
      (node (ref "AC0") (pin "A") (pinfunction "A_A") (pintype "passive"))
      (node (ref "R43") (pin "2") (pinfunction "2_2") (pintype "passive"))
    )
    (net (code "71") (name "Net-(AC0-PadB)") (class "Default")
      (node (ref "AC0") (pin "B") (pinfunction "B_B") (pintype "passive"))
      (node (ref "T43") (pin "C") (pinfunction "C_C") (pintype "passive"))
    )
    (net (code "72") (name "Net-(AC1-PadA)") (class "Default")
      (node (ref "AC1") (pin "A") (pinfunction "A_A") (pintype "passive"))
      (node (ref "R44") (pin "2") (pinfunction "2_2") (pintype "passive"))
    )
    (net (code "73") (name "Net-(AC1-PadB)") (class "Default")
      (node (ref "AC1") (pin "B") (pinfunction "B_B") (pintype "passive"))
      (node (ref "T44") (pin "C") (pinfunction "C_C") (pintype "passive"))
    )
    (net (code "74") (name "Net-(AC2-PadA)") (class "Default")
      (node (ref "AC2") (pin "A") (pinfunction "A_A") (pintype "passive"))
      (node (ref "R45") (pin "2") (pinfunction "2_2") (pintype "passive"))
    )
    (net (code "75") (name "Net-(AC2-PadB)") (class "Default")
      (node (ref "AC2") (pin "B") (pinfunction "B_B") (pintype "passive"))
      (node (ref "T45") (pin "C") (pinfunction "C_C") (pintype "passive"))
    )
    (net (code "76") (name "Net-(AC3-PadA)") (class "Default")
      (node (ref "AC3") (pin "A") (pinfunction "A_A") (pintype "passive"))
      (node (ref "R46") (pin "2") (pinfunction "2_2") (pintype "passive"))
    )
    (net (code "77") (name "Net-(AC3-PadB)") (class "Default")
      (node (ref "AC3") (pin "B") (pinfunction "B_B") (pintype "passive"))
      (node (ref "T46") (pin "C") (pinfunction "C_C") (pintype "passive"))
    )
    (net (code "78") (name "Net-(AC4-PadA)") (class "Default")
      (node (ref "AC4") (pin "A") (pinfunction "A_A") (pintype "passive"))
      (node (ref "R47") (pin "2") (pinfunction "2_2") (pintype "passive"))
    )
    (net (code "79") (name "Net-(AC4-PadB)") (class "Default")
      (node (ref "AC4") (pin "B") (pinfunction "B_B") (pintype "passive"))
      (node (ref "T47") (pin "C") (pinfunction "C_C") (pintype "passive"))
    )
    (net (code "80") (name "Net-(AC5-PadA)") (class "Default")
      (node (ref "AC5") (pin "A") (pinfunction "A_A") (pintype "passive"))
      (node (ref "R48") (pin "2") (pinfunction "2_2") (pintype "passive"))
    )
    (net (code "81") (name "Net-(AC5-PadB)") (class "Default")
      (node (ref "AC5") (pin "B") (pinfunction "B_B") (pintype "passive"))
      (node (ref "T48") (pin "C") (pinfunction "C_C") (pintype "passive"))
    )
    (net (code "82") (name "Net-(AC6-PadA)") (class "Default")
      (node (ref "AC6") (pin "A") (pinfunction "A_A") (pintype "passive"))
      (node (ref "R49") (pin "2") (pinfunction "2_2") (pintype "passive"))
    )
    (net (code "83") (name "Net-(AC6-PadB)") (class "Default")
      (node (ref "AC6") (pin "B") (pinfunction "B_B") (pintype "passive"))
      (node (ref "T49") (pin "C") (pinfunction "C_C") (pintype "passive"))
    )
    (net (code "84") (name "Net-(AC7-PadA)") (class "Default")
      (node (ref "AC7") (pin "A") (pinfunction "A_A") (pintype "passive"))
      (node (ref "R50") (pin "2") (pinfunction "2_2") (pintype "passive"))
    )
    (net (code "85") (name "Net-(AC7-PadB)") (class "Default")
      (node (ref "AC7") (pin "B") (pinfunction "B_B") (pintype "passive"))
      (node (ref "T50") (pin "C") (pinfunction "C_C") (pintype "passive"))
    )
    (net (code "86") (name "Net-(AC8-PadA)") (class "Default")
      (node (ref "AC8") (pin "A") (pinfunction "A_A") (pintype "passive"))
      (node (ref "R51") (pin "2") (pinfunction "2_2") (pintype "passive"))
    )
    (net (code "87") (name "Net-(AC8-PadB)") (class "Default")
      (node (ref "AC8") (pin "B") (pinfunction "B_B") (pintype "passive"))
      (node (ref "T51") (pin "C") (pinfunction "C_C") (pintype "passive"))
    )
    (net (code "88") (name "Net-(AC9-PadA)") (class "Default")
      (node (ref "AC9") (pin "A") (pinfunction "A_A") (pintype "passive"))
      (node (ref "R52") (pin "2") (pinfunction "2_2") (pintype "passive"))
    )
    (net (code "89") (name "Net-(AC9-PadB)") (class "Default")
      (node (ref "AC9") (pin "B") (pinfunction "B_B") (pintype "passive"))
      (node (ref "T52") (pin "C") (pinfunction "C_C") (pintype "passive"))
    )
    (net (code "90") (name "Net-(AC10-PadA)") (class "Default")
      (node (ref "AC10") (pin "A") (pinfunction "A_A") (pintype "passive"))
      (node (ref "R53") (pin "2") (pinfunction "2_2") (pintype "passive"))
    )
    (net (code "91") (name "Net-(AC10-PadB)") (class "Default")
      (node (ref "AC10") (pin "B") (pinfunction "B_B") (pintype "passive"))
      (node (ref "T53") (pin "C") (pinfunction "C_C") (pintype "passive"))
    )
    (net (code "92") (name "Net-(AC11-PadA)") (class "Default")
      (node (ref "AC11") (pin "A") (pinfunction "A_A") (pintype "passive"))
      (node (ref "R54") (pin "2") (pinfunction "2_2") (pintype "passive"))
    )
    (net (code "93") (name "Net-(AC11-PadB)") (class "Default")
      (node (ref "AC11") (pin "B") (pinfunction "B_B") (pintype "passive"))
      (node (ref "T54") (pin "C") (pinfunction "C_C") (pintype "passive"))
    )
    (net (code "94") (name "Net-(AND-PadA)") (class "Default")
      (node (ref "AND") (pin "A") (pinfunction "A_A") (pintype "passive"))
      (node (ref "R82") (pin "2") (pinfunction "2_2") (pintype "passive"))
    )
    (net (code "95") (name "Net-(AND-PadB)") (class "Default")
      (node (ref "AND") (pin "B") (pinfunction "B_B") (pintype "passive"))
      (node (ref "T82") (pin "C") (pinfunction "C_C") (pintype "passive"))
    )
    (net (code "96") (name "Net-(BREAK-PadA)") (class "Default")
      (node (ref "BREAK") (pin "A") (pinfunction "A_A") (pintype "passive"))
      (node (ref "R81") (pin "2") (pinfunction "2_2") (pintype "passive"))
    )
    (net (code "97") (name "Net-(BREAK-PadB)") (class "Default")
      (node (ref "BREAK") (pin "B") (pinfunction "B_B") (pintype "passive"))
      (node (ref "T81") (pin "C") (pinfunction "C_C") (pintype "passive"))
    )
    (net (code "98") (name "Net-(CURRENTADDRESS-PadA)") (class "Default")
      (node (ref "CURRENTADDRESS") (pin "A") (pinfunction "A_A") (pintype "passive"))
      (node (ref "R80") (pin "2") (pinfunction "2_2") (pintype "passive"))
    )
    (net (code "99") (name "Net-(CURRENTADDRESS-PadB)") (class "Default")
      (node (ref "CURRENTADDRESS") (pin "B") (pinfunction "B_B") (pintype "passive"))
      (node (ref "T80") (pin "C") (pinfunction "C_C") (pintype "passive"))
    )
    (net (code "100") (name "Net-(DCA-PadA)") (class "Default")
      (node (ref "DCA") (pin "A") (pinfunction "A_A") (pintype "passive"))
      (node (ref "R85") (pin "2") (pinfunction "2_2") (pintype "passive"))
    )
    (net (code "101") (name "Net-(DCA-PadB)") (class "Default")
      (node (ref "DCA") (pin "B") (pinfunction "B_B") (pintype "passive"))
      (node (ref "T85") (pin "C") (pinfunction "C_C") (pintype "passive"))
    )
    (net (code "102") (name "Net-(DEFER-PadA)") (class "Default")
      (node (ref "DEFER") (pin "A") (pinfunction "A_A") (pintype "passive"))
      (node (ref "R78") (pin "2") (pinfunction "2_2") (pintype "passive"))
    )
    (net (code "103") (name "Net-(DEFER-PadB)") (class "Default")
      (node (ref "DEFER") (pin "B") (pinfunction "B_B") (pintype "passive"))
      (node (ref "T78") (pin "C") (pinfunction "C_C") (pintype "passive"))
    )
    (net (code "104") (name "Net-(DF0-PadA)") (class "Default")
      (node (ref "DF0") (pin "A") (pinfunction "A_A") (pintype "passive"))
      (node (ref "R1") (pin "2") (pinfunction "2_2") (pintype "passive"))
    )
    (net (code "105") (name "Net-(DF0-PadB)") (class "Default")
      (node (ref "DF0") (pin "B") (pinfunction "B_B") (pintype "passive"))
      (node (ref "T1") (pin "C") (pinfunction "C_C") (pintype "passive"))
    )
    (net (code "106") (name "Net-(DF1-PadA)") (class "Default")
      (node (ref "DF1") (pin "A") (pinfunction "A_A") (pintype "passive"))
      (node (ref "R2") (pin "2") (pinfunction "2_2") (pintype "passive"))
    )
    (net (code "107") (name "Net-(DF1-PadB)") (class "Default")
      (node (ref "DF1") (pin "B") (pinfunction "B_B") (pintype "passive"))
      (node (ref "T2") (pin "C") (pinfunction "C_C") (pintype "passive"))
    )
    (net (code "108") (name "Net-(DF2-PadA)") (class "Default")
      (node (ref "DF2") (pin "A") (pinfunction "A_A") (pintype "passive"))
      (node (ref "R3") (pin "2") (pinfunction "2_2") (pintype "passive"))
    )
    (net (code "109") (name "Net-(DF2-PadB)") (class "Default")
      (node (ref "DF2") (pin "B") (pinfunction "B_B") (pintype "passive"))
      (node (ref "T3") (pin "C") (pinfunction "C_C") (pintype "passive"))
    )
    (net (code "110") (name "Net-(EXECUTE-PadA)") (class "Default")
      (node (ref "EXECUTE") (pin "A") (pinfunction "A_A") (pintype "passive"))
      (node (ref "R77") (pin "2") (pinfunction "2_2") (pintype "passive"))
    )
    (net (code "111") (name "Net-(EXECUTE-PadB)") (class "Default")
      (node (ref "EXECUTE") (pin "B") (pinfunction "B_B") (pintype "passive"))
      (node (ref "T77") (pin "C") (pinfunction "C_C") (pintype "passive"))
    )
    (net (code "112") (name "Net-(FETCH-PadA)") (class "Default")
      (node (ref "FETCH") (pin "A") (pinfunction "A_A") (pintype "passive"))
      (node (ref "R76") (pin "2") (pinfunction "2_2") (pintype "passive"))
    )
    (net (code "113") (name "Net-(FETCH-PadB)") (class "Default")
      (node (ref "FETCH") (pin "B") (pinfunction "B_B") (pintype "passive"))
      (node (ref "T76") (pin "C") (pinfunction "C_C") (pintype "passive"))
    )
    (net (code "114") (name "Net-(IF0-PadA)") (class "Default")
      (node (ref "IF0") (pin "A") (pinfunction "A_A") (pintype "passive"))
      (node (ref "R4") (pin "2") (pinfunction "2_2") (pintype "passive"))
    )
    (net (code "115") (name "Net-(IF0-PadB)") (class "Default")
      (node (ref "IF0") (pin "B") (pinfunction "B_B") (pintype "passive"))
      (node (ref "T4") (pin "C") (pinfunction "C_C") (pintype "passive"))
    )
    (net (code "116") (name "Net-(IF1-PadA)") (class "Default")
      (node (ref "IF1") (pin "A") (pinfunction "A_A") (pintype "passive"))
      (node (ref "R5") (pin "2") (pinfunction "2_2") (pintype "passive"))
    )
    (net (code "117") (name "Net-(IF1-PadB)") (class "Default")
      (node (ref "IF1") (pin "B") (pinfunction "B_B") (pintype "passive"))
      (node (ref "T5") (pin "C") (pinfunction "C_C") (pintype "passive"))
    )
    (net (code "118") (name "Net-(IF2-PadA)") (class "Default")
      (node (ref "IF2") (pin "A") (pinfunction "A_A") (pintype "passive"))
      (node (ref "R6") (pin "2") (pinfunction "2_2") (pintype "passive"))
    )
    (net (code "119") (name "Net-(IF2-PadB)") (class "Default")
      (node (ref "IF2") (pin "B") (pinfunction "B_B") (pintype "passive"))
      (node (ref "T6") (pin "C") (pinfunction "C_C") (pintype "passive"))
    )
    (net (code "120") (name "Net-(ION-PadA)") (class "Default")
      (node (ref "ION") (pin "A") (pinfunction "A_A") (pintype "passive"))
      (node (ref "R73") (pin "2") (pinfunction "2_2") (pintype "passive"))
    )
    (net (code "121") (name "Net-(ION-PadB)") (class "Default")
      (node (ref "ION") (pin "B") (pinfunction "B_B") (pintype "passive"))
      (node (ref "T73") (pin "C") (pinfunction "C_C") (pintype "passive"))
    )
    (net (code "122") (name "Net-(IOT-PadA)") (class "Default")
      (node (ref "IOT") (pin "A") (pinfunction "A_A") (pintype "passive"))
      (node (ref "R88") (pin "2") (pinfunction "2_2") (pintype "passive"))
    )
    (net (code "123") (name "Net-(IOT-PadB)") (class "Default")
      (node (ref "IOT") (pin "B") (pinfunction "B_B") (pintype "passive"))
      (node (ref "T88") (pin "C") (pinfunction "C_C") (pintype "passive"))
    )
    (net (code "124") (name "Net-(ISZ-PadA)") (class "Default")
      (node (ref "ISZ") (pin "A") (pinfunction "A_A") (pintype "passive"))
      (node (ref "R84") (pin "2") (pinfunction "2_2") (pintype "passive"))
    )
    (net (code "125") (name "Net-(ISZ-PadB)") (class "Default")
      (node (ref "ISZ") (pin "B") (pinfunction "B_B") (pintype "passive"))
      (node (ref "T84") (pin "C") (pinfunction "C_C") (pintype "passive"))
    )
    (net (code "126") (name "Net-(JMP-PadA)") (class "Default")
      (node (ref "JMP") (pin "A") (pinfunction "A_A") (pintype "passive"))
      (node (ref "R87") (pin "2") (pinfunction "2_2") (pintype "passive"))
    )
    (net (code "127") (name "Net-(JMP-PadB)") (class "Default")
      (node (ref "JMP") (pin "B") (pinfunction "B_B") (pintype "passive"))
      (node (ref "T87") (pin "C") (pinfunction "C_C") (pintype "passive"))
    )
    (net (code "128") (name "Net-(JMS-PadA)") (class "Default")
      (node (ref "JMS") (pin "A") (pinfunction "A_A") (pintype "passive"))
      (node (ref "R86") (pin "2") (pinfunction "2_2") (pintype "passive"))
    )
    (net (code "129") (name "Net-(JMS-PadB)") (class "Default")
      (node (ref "JMS") (pin "B") (pinfunction "B_B") (pintype "passive"))
      (node (ref "T86") (pin "C") (pinfunction "C_C") (pintype "passive"))
    )
    (net (code "130") (name "Net-(LINK-PadA)") (class "Default")
      (node (ref "LINK") (pin "A") (pinfunction "A_A") (pintype "passive"))
      (node (ref "R72") (pin "2") (pinfunction "2_2") (pintype "passive"))
    )
    (net (code "131") (name "Net-(LINK-PadB)") (class "Default")
      (node (ref "LINK") (pin "B") (pinfunction "B_B") (pintype "passive"))
      (node (ref "T72") (pin "C") (pinfunction "C_C") (pintype "passive"))
    )
    (net (code "132") (name "Net-(MA0-PadA)") (class "Default")
      (node (ref "MA0") (pin "A") (pinfunction "A_A") (pintype "passive"))
      (node (ref "R19") (pin "2") (pinfunction "2_2") (pintype "passive"))
    )
    (net (code "133") (name "Net-(MA0-PadB)") (class "Default")
      (node (ref "MA0") (pin "B") (pinfunction "B_B") (pintype "passive"))
      (node (ref "T19") (pin "C") (pinfunction "C_C") (pintype "passive"))
    )
    (net (code "134") (name "Net-(MA1-PadA)") (class "Default")
      (node (ref "MA1") (pin "A") (pinfunction "A_A") (pintype "passive"))
      (node (ref "R20") (pin "2") (pinfunction "2_2") (pintype "passive"))
    )
    (net (code "135") (name "Net-(MA1-PadB)") (class "Default")
      (node (ref "MA1") (pin "B") (pinfunction "B_B") (pintype "passive"))
      (node (ref "T20") (pin "C") (pinfunction "C_C") (pintype "passive"))
    )
    (net (code "136") (name "Net-(MA2-PadA)") (class "Default")
      (node (ref "MA2") (pin "A") (pinfunction "A_A") (pintype "passive"))
      (node (ref "R21") (pin "2") (pinfunction "2_2") (pintype "passive"))
    )
    (net (code "137") (name "Net-(MA2-PadB)") (class "Default")
      (node (ref "MA2") (pin "B") (pinfunction "B_B") (pintype "passive"))
      (node (ref "T21") (pin "C") (pinfunction "C_C") (pintype "passive"))
    )
    (net (code "138") (name "Net-(MA3-PadA)") (class "Default")
      (node (ref "MA3") (pin "A") (pinfunction "A_A") (pintype "passive"))
      (node (ref "R22") (pin "2") (pinfunction "2_2") (pintype "passive"))
    )
    (net (code "139") (name "Net-(MA3-PadB)") (class "Default")
      (node (ref "MA3") (pin "B") (pinfunction "B_B") (pintype "passive"))
      (node (ref "T22") (pin "C") (pinfunction "C_C") (pintype "passive"))
    )
    (net (code "140") (name "Net-(MA4-PadA)") (class "Default")
      (node (ref "MA4") (pin "A") (pinfunction "A_A") (pintype "passive"))
      (node (ref "R23") (pin "2") (pinfunction "2_2") (pintype "passive"))
    )
    (net (code "141") (name "Net-(MA4-PadB)") (class "Default")
      (node (ref "MA4") (pin "B") (pinfunction "B_B") (pintype "passive"))
      (node (ref "T23") (pin "C") (pinfunction "C_C") (pintype "passive"))
    )
    (net (code "142") (name "Net-(MA5-PadA)") (class "Default")
      (node (ref "MA5") (pin "A") (pinfunction "A_A") (pintype "passive"))
      (node (ref "R24") (pin "2") (pinfunction "2_2") (pintype "passive"))
    )
    (net (code "143") (name "Net-(MA5-PadB)") (class "Default")
      (node (ref "MA5") (pin "B") (pinfunction "B_B") (pintype "passive"))
      (node (ref "T24") (pin "C") (pinfunction "C_C") (pintype "passive"))
    )
    (net (code "144") (name "Net-(MA6-PadA)") (class "Default")
      (node (ref "MA6") (pin "A") (pinfunction "A_A") (pintype "passive"))
      (node (ref "R25") (pin "2") (pinfunction "2_2") (pintype "passive"))
    )
    (net (code "145") (name "Net-(MA6-PadB)") (class "Default")
      (node (ref "MA6") (pin "B") (pinfunction "B_B") (pintype "passive"))
      (node (ref "T25") (pin "C") (pinfunction "C_C") (pintype "passive"))
    )
    (net (code "146") (name "Net-(MA7-PadA)") (class "Default")
      (node (ref "MA7") (pin "A") (pinfunction "A_A") (pintype "passive"))
      (node (ref "R26") (pin "2") (pinfunction "2_2") (pintype "passive"))
    )
    (net (code "147") (name "Net-(MA7-PadB)") (class "Default")
      (node (ref "MA7") (pin "B") (pinfunction "B_B") (pintype "passive"))
      (node (ref "T26") (pin "C") (pinfunction "C_C") (pintype "passive"))
    )
    (net (code "148") (name "Net-(MA8-PadA)") (class "Default")
      (node (ref "MA8") (pin "A") (pinfunction "A_A") (pintype "passive"))
      (node (ref "R27") (pin "2") (pinfunction "2_2") (pintype "passive"))
    )
    (net (code "149") (name "Net-(MA8-PadB)") (class "Default")
      (node (ref "MA8") (pin "B") (pinfunction "B_B") (pintype "passive"))
      (node (ref "T27") (pin "C") (pinfunction "C_C") (pintype "passive"))
    )
    (net (code "150") (name "Net-(MA9-PadA)") (class "Default")
      (node (ref "MA9") (pin "A") (pinfunction "A_A") (pintype "passive"))
      (node (ref "R28") (pin "2") (pinfunction "2_2") (pintype "passive"))
    )
    (net (code "151") (name "Net-(MA9-PadB)") (class "Default")
      (node (ref "MA9") (pin "B") (pinfunction "B_B") (pintype "passive"))
      (node (ref "T28") (pin "C") (pinfunction "C_C") (pintype "passive"))
    )
    (net (code "152") (name "Net-(MA10-PadA)") (class "Default")
      (node (ref "MA10") (pin "A") (pinfunction "A_A") (pintype "passive"))
      (node (ref "R29") (pin "2") (pinfunction "2_2") (pintype "passive"))
    )
    (net (code "153") (name "Net-(MA10-PadB)") (class "Default")
      (node (ref "MA10") (pin "B") (pinfunction "B_B") (pintype "passive"))
      (node (ref "T29") (pin "C") (pinfunction "C_C") (pintype "passive"))
    )
    (net (code "154") (name "Net-(MA11-PadA)") (class "Default")
      (node (ref "MA11") (pin "A") (pinfunction "A_A") (pintype "passive"))
      (node (ref "R30") (pin "2") (pinfunction "2_2") (pintype "passive"))
    )
    (net (code "155") (name "Net-(MA11-PadB)") (class "Default")
      (node (ref "MA11") (pin "B") (pinfunction "B_B") (pintype "passive"))
      (node (ref "T30") (pin "C") (pinfunction "C_C") (pintype "passive"))
    )
    (net (code "156") (name "Net-(MB0-PadA)") (class "Default")
      (node (ref "MB0") (pin "A") (pinfunction "A_A") (pintype "passive"))
      (node (ref "R31") (pin "2") (pinfunction "2_2") (pintype "passive"))
    )
    (net (code "157") (name "Net-(MB0-PadB)") (class "Default")
      (node (ref "MB0") (pin "B") (pinfunction "B_B") (pintype "passive"))
      (node (ref "T31") (pin "C") (pinfunction "C_C") (pintype "passive"))
    )
    (net (code "158") (name "Net-(MB1-PadA)") (class "Default")
      (node (ref "MB1") (pin "A") (pinfunction "A_A") (pintype "passive"))
      (node (ref "R32") (pin "2") (pinfunction "2_2") (pintype "passive"))
    )
    (net (code "159") (name "Net-(MB1-PadB)") (class "Default")
      (node (ref "MB1") (pin "B") (pinfunction "B_B") (pintype "passive"))
      (node (ref "T32") (pin "C") (pinfunction "C_C") (pintype "passive"))
    )
    (net (code "160") (name "Net-(MB2-PadA)") (class "Default")
      (node (ref "MB2") (pin "A") (pinfunction "A_A") (pintype "passive"))
      (node (ref "R33") (pin "2") (pinfunction "2_2") (pintype "passive"))
    )
    (net (code "161") (name "Net-(MB2-PadB)") (class "Default")
      (node (ref "MB2") (pin "B") (pinfunction "B_B") (pintype "passive"))
      (node (ref "T33") (pin "C") (pinfunction "C_C") (pintype "passive"))
    )
    (net (code "162") (name "Net-(MB3-PadA)") (class "Default")
      (node (ref "MB3") (pin "A") (pinfunction "A_A") (pintype "passive"))
      (node (ref "R34") (pin "2") (pinfunction "2_2") (pintype "passive"))
    )
    (net (code "163") (name "Net-(MB3-PadB)") (class "Default")
      (node (ref "MB3") (pin "B") (pinfunction "B_B") (pintype "passive"))
      (node (ref "T34") (pin "C") (pinfunction "C_C") (pintype "passive"))
    )
    (net (code "164") (name "Net-(MB4-PadA)") (class "Default")
      (node (ref "MB4") (pin "A") (pinfunction "A_A") (pintype "passive"))
      (node (ref "R35") (pin "2") (pinfunction "2_2") (pintype "passive"))
    )
    (net (code "165") (name "Net-(MB4-PadB)") (class "Default")
      (node (ref "MB4") (pin "B") (pinfunction "B_B") (pintype "passive"))
      (node (ref "T35") (pin "C") (pinfunction "C_C") (pintype "passive"))
    )
    (net (code "166") (name "Net-(MB5-PadA)") (class "Default")
      (node (ref "MB5") (pin "A") (pinfunction "A_A") (pintype "passive"))
      (node (ref "R36") (pin "2") (pinfunction "2_2") (pintype "passive"))
    )
    (net (code "167") (name "Net-(MB5-PadB)") (class "Default")
      (node (ref "MB5") (pin "B") (pinfunction "B_B") (pintype "passive"))
      (node (ref "T36") (pin "C") (pinfunction "C_C") (pintype "passive"))
    )
    (net (code "168") (name "Net-(MB6-PadA)") (class "Default")
      (node (ref "MB6") (pin "A") (pinfunction "A_A") (pintype "passive"))
      (node (ref "R37") (pin "2") (pinfunction "2_2") (pintype "passive"))
    )
    (net (code "169") (name "Net-(MB6-PadB)") (class "Default")
      (node (ref "MB6") (pin "B") (pinfunction "B_B") (pintype "passive"))
      (node (ref "T37") (pin "C") (pinfunction "C_C") (pintype "passive"))
    )
    (net (code "170") (name "Net-(MB7-PadA)") (class "Default")
      (node (ref "MB7") (pin "A") (pinfunction "A_A") (pintype "passive"))
      (node (ref "R38") (pin "2") (pinfunction "2_2") (pintype "passive"))
    )
    (net (code "171") (name "Net-(MB7-PadB)") (class "Default")
      (node (ref "MB7") (pin "B") (pinfunction "B_B") (pintype "passive"))
      (node (ref "T38") (pin "C") (pinfunction "C_C") (pintype "passive"))
    )
    (net (code "172") (name "Net-(MB8-PadA)") (class "Default")
      (node (ref "MB8") (pin "A") (pinfunction "A_A") (pintype "passive"))
      (node (ref "R39") (pin "2") (pinfunction "2_2") (pintype "passive"))
    )
    (net (code "173") (name "Net-(MB8-PadB)") (class "Default")
      (node (ref "MB8") (pin "B") (pinfunction "B_B") (pintype "passive"))
      (node (ref "T39") (pin "C") (pinfunction "C_C") (pintype "passive"))
    )
    (net (code "174") (name "Net-(MB9-PadA)") (class "Default")
      (node (ref "MB9") (pin "A") (pinfunction "A_A") (pintype "passive"))
      (node (ref "R40") (pin "2") (pinfunction "2_2") (pintype "passive"))
    )
    (net (code "175") (name "Net-(MB9-PadB)") (class "Default")
      (node (ref "MB9") (pin "B") (pinfunction "B_B") (pintype "passive"))
      (node (ref "T40") (pin "C") (pinfunction "C_C") (pintype "passive"))
    )
    (net (code "176") (name "Net-(MB10-PadA)") (class "Default")
      (node (ref "MB10") (pin "A") (pinfunction "A_A") (pintype "passive"))
      (node (ref "R41") (pin "2") (pinfunction "2_2") (pintype "passive"))
    )
    (net (code "177") (name "Net-(MB10-PadB)") (class "Default")
      (node (ref "MB10") (pin "B") (pinfunction "B_B") (pintype "passive"))
      (node (ref "T41") (pin "C") (pinfunction "C_C") (pintype "passive"))
    )
    (net (code "178") (name "Net-(MB11-PadA)") (class "Default")
      (node (ref "MB11") (pin "A") (pinfunction "A_A") (pintype "passive"))
      (node (ref "R42") (pin "2") (pinfunction "2_2") (pintype "passive"))
    )
    (net (code "179") (name "Net-(MB11-PadB)") (class "Default")
      (node (ref "MB11") (pin "B") (pinfunction "B_B") (pintype "passive"))
      (node (ref "T42") (pin "C") (pinfunction "C_C") (pintype "passive"))
    )
    (net (code "180") (name "Net-(MQ0-PadA)") (class "Default")
      (node (ref "MQ0") (pin "A") (pinfunction "A_A") (pintype "passive"))
      (node (ref "R55") (pin "2") (pinfunction "2_2") (pintype "passive"))
    )
    (net (code "181") (name "Net-(MQ0-PadB)") (class "Default")
      (node (ref "MQ0") (pin "B") (pinfunction "B_B") (pintype "passive"))
      (node (ref "T55") (pin "C") (pinfunction "C_C") (pintype "passive"))
    )
    (net (code "182") (name "Net-(MQ1-PadA)") (class "Default")
      (node (ref "MQ1") (pin "A") (pinfunction "A_A") (pintype "passive"))
      (node (ref "R56") (pin "2") (pinfunction "2_2") (pintype "passive"))
    )
    (net (code "183") (name "Net-(MQ1-PadB)") (class "Default")
      (node (ref "MQ1") (pin "B") (pinfunction "B_B") (pintype "passive"))
      (node (ref "T56") (pin "C") (pinfunction "C_C") (pintype "passive"))
    )
    (net (code "184") (name "Net-(MQ2-PadA)") (class "Default")
      (node (ref "MQ2") (pin "A") (pinfunction "A_A") (pintype "passive"))
      (node (ref "R57") (pin "2") (pinfunction "2_2") (pintype "passive"))
    )
    (net (code "185") (name "Net-(MQ2-PadB)") (class "Default")
      (node (ref "MQ2") (pin "B") (pinfunction "B_B") (pintype "passive"))
      (node (ref "T57") (pin "C") (pinfunction "C_C") (pintype "passive"))
    )
    (net (code "186") (name "Net-(MQ3-PadA)") (class "Default")
      (node (ref "MQ3") (pin "A") (pinfunction "A_A") (pintype "passive"))
      (node (ref "R58") (pin "2") (pinfunction "2_2") (pintype "passive"))
    )
    (net (code "187") (name "Net-(MQ3-PadB)") (class "Default")
      (node (ref "MQ3") (pin "B") (pinfunction "B_B") (pintype "passive"))
      (node (ref "T58") (pin "C") (pinfunction "C_C") (pintype "passive"))
    )
    (net (code "188") (name "Net-(MQ4-PadA)") (class "Default")
      (node (ref "MQ4") (pin "A") (pinfunction "A_A") (pintype "passive"))
      (node (ref "R59") (pin "2") (pinfunction "2_2") (pintype "passive"))
    )
    (net (code "189") (name "Net-(MQ4-PadB)") (class "Default")
      (node (ref "MQ4") (pin "B") (pinfunction "B_B") (pintype "passive"))
      (node (ref "T59") (pin "C") (pinfunction "C_C") (pintype "passive"))
    )
    (net (code "190") (name "Net-(MQ5-PadA)") (class "Default")
      (node (ref "MQ5") (pin "A") (pinfunction "A_A") (pintype "passive"))
      (node (ref "R60") (pin "2") (pinfunction "2_2") (pintype "passive"))
    )
    (net (code "191") (name "Net-(MQ5-PadB)") (class "Default")
      (node (ref "MQ5") (pin "B") (pinfunction "B_B") (pintype "passive"))
      (node (ref "T60") (pin "C") (pinfunction "C_C") (pintype "passive"))
    )
    (net (code "192") (name "Net-(MQ6-PadA)") (class "Default")
      (node (ref "MQ6") (pin "A") (pinfunction "A_A") (pintype "passive"))
      (node (ref "R61") (pin "2") (pinfunction "2_2") (pintype "passive"))
    )
    (net (code "193") (name "Net-(MQ6-PadB)") (class "Default")
      (node (ref "MQ6") (pin "B") (pinfunction "B_B") (pintype "passive"))
      (node (ref "T61") (pin "C") (pinfunction "C_C") (pintype "passive"))
    )
    (net (code "194") (name "Net-(MQ7-PadA)") (class "Default")
      (node (ref "MQ7") (pin "A") (pinfunction "A_A") (pintype "passive"))
      (node (ref "R62") (pin "2") (pinfunction "2_2") (pintype "passive"))
    )
    (net (code "195") (name "Net-(MQ7-PadB)") (class "Default")
      (node (ref "MQ7") (pin "B") (pinfunction "B_B") (pintype "passive"))
      (node (ref "T62") (pin "C") (pinfunction "C_C") (pintype "passive"))
    )
    (net (code "196") (name "Net-(MQ8-PadA)") (class "Default")
      (node (ref "MQ8") (pin "A") (pinfunction "A_A") (pintype "passive"))
      (node (ref "R63") (pin "2") (pinfunction "2_2") (pintype "passive"))
    )
    (net (code "197") (name "Net-(MQ8-PadB)") (class "Default")
      (node (ref "MQ8") (pin "B") (pinfunction "B_B") (pintype "passive"))
      (node (ref "T63") (pin "C") (pinfunction "C_C") (pintype "passive"))
    )
    (net (code "198") (name "Net-(MQ9-PadA)") (class "Default")
      (node (ref "MQ9") (pin "A") (pinfunction "A_A") (pintype "passive"))
      (node (ref "R64") (pin "2") (pinfunction "2_2") (pintype "passive"))
    )
    (net (code "199") (name "Net-(MQ9-PadB)") (class "Default")
      (node (ref "MQ9") (pin "B") (pinfunction "B_B") (pintype "passive"))
      (node (ref "T64") (pin "C") (pinfunction "C_C") (pintype "passive"))
    )
    (net (code "200") (name "Net-(MQ10-PadA)") (class "Default")
      (node (ref "MQ10") (pin "A") (pinfunction "A_A") (pintype "passive"))
      (node (ref "R65") (pin "2") (pinfunction "2_2") (pintype "passive"))
    )
    (net (code "201") (name "Net-(MQ10-PadB)") (class "Default")
      (node (ref "MQ10") (pin "B") (pinfunction "B_B") (pintype "passive"))
      (node (ref "T65") (pin "C") (pinfunction "C_C") (pintype "passive"))
    )
    (net (code "202") (name "Net-(MQ11-PadA)") (class "Default")
      (node (ref "MQ11") (pin "A") (pinfunction "A_A") (pintype "passive"))
      (node (ref "R66") (pin "2") (pinfunction "2_2") (pintype "passive"))
    )
    (net (code "203") (name "Net-(MQ11-PadB)") (class "Default")
      (node (ref "MQ11") (pin "B") (pinfunction "B_B") (pintype "passive"))
      (node (ref "T66") (pin "C") (pinfunction "C_C") (pintype "passive"))
    )
    (net (code "204") (name "Net-(OPR-PadA)") (class "Default")
      (node (ref "OPR") (pin "A") (pinfunction "A_A") (pintype "passive"))
      (node (ref "R89") (pin "2") (pinfunction "2_2") (pintype "passive"))
    )
    (net (code "205") (name "Net-(OPR-PadB)") (class "Default")
      (node (ref "OPR") (pin "B") (pinfunction "B_B") (pintype "passive"))
      (node (ref "T89") (pin "C") (pinfunction "C_C") (pintype "passive"))
    )
    (net (code "206") (name "Net-(PAUSE-PadA)") (class "Default")
      (node (ref "PAUSE") (pin "A") (pinfunction "A_A") (pintype "passive"))
      (node (ref "R74") (pin "2") (pinfunction "2_2") (pintype "passive"))
    )
    (net (code "207") (name "Net-(PAUSE-PadB)") (class "Default")
      (node (ref "PAUSE") (pin "B") (pinfunction "B_B") (pintype "passive"))
      (node (ref "T74") (pin "C") (pinfunction "C_C") (pintype "passive"))
    )
    (net (code "208") (name "Net-(PC0-PadA)") (class "Default")
      (node (ref "PC0") (pin "A") (pinfunction "A_A") (pintype "passive"))
      (node (ref "R7") (pin "2") (pinfunction "2_2") (pintype "passive"))
    )
    (net (code "209") (name "Net-(PC0-PadB)") (class "Default")
      (node (ref "PC0") (pin "B") (pinfunction "B_B") (pintype "passive"))
      (node (ref "T7") (pin "C") (pinfunction "C_C") (pintype "passive"))
    )
    (net (code "210") (name "Net-(PC1-PadA)") (class "Default")
      (node (ref "PC1") (pin "A") (pinfunction "A_A") (pintype "passive"))
      (node (ref "R8") (pin "2") (pinfunction "2_2") (pintype "passive"))
    )
    (net (code "211") (name "Net-(PC1-PadB)") (class "Default")
      (node (ref "PC1") (pin "B") (pinfunction "B_B") (pintype "passive"))
      (node (ref "T8") (pin "C") (pinfunction "C_C") (pintype "passive"))
    )
    (net (code "212") (name "Net-(PC2-PadA)") (class "Default")
      (node (ref "PC2") (pin "A") (pinfunction "A_A") (pintype "passive"))
      (node (ref "R9") (pin "2") (pinfunction "2_2") (pintype "passive"))
    )
    (net (code "213") (name "Net-(PC2-PadB)") (class "Default")
      (node (ref "PC2") (pin "B") (pinfunction "B_B") (pintype "passive"))
      (node (ref "T9") (pin "C") (pinfunction "C_C") (pintype "passive"))
    )
    (net (code "214") (name "Net-(PC3-PadA)") (class "Default")
      (node (ref "PC3") (pin "A") (pinfunction "A_A") (pintype "passive"))
      (node (ref "R10") (pin "2") (pinfunction "2_2") (pintype "passive"))
    )
    (net (code "215") (name "Net-(PC3-PadB)") (class "Default")
      (node (ref "PC3") (pin "B") (pinfunction "B_B") (pintype "passive"))
      (node (ref "T10") (pin "C") (pinfunction "C_C") (pintype "passive"))
    )
    (net (code "216") (name "Net-(PC4-PadA)") (class "Default")
      (node (ref "PC4") (pin "A") (pinfunction "A_A") (pintype "passive"))
      (node (ref "R11") (pin "2") (pinfunction "2_2") (pintype "passive"))
    )
    (net (code "217") (name "Net-(PC4-PadB)") (class "Default")
      (node (ref "PC4") (pin "B") (pinfunction "B_B") (pintype "passive"))
      (node (ref "T11") (pin "C") (pinfunction "C_C") (pintype "passive"))
    )
    (net (code "218") (name "Net-(PC5-PadA)") (class "Default")
      (node (ref "PC5") (pin "A") (pinfunction "A_A") (pintype "passive"))
      (node (ref "R12") (pin "2") (pinfunction "2_2") (pintype "passive"))
    )
    (net (code "219") (name "Net-(PC5-PadB)") (class "Default")
      (node (ref "PC5") (pin "B") (pinfunction "B_B") (pintype "passive"))
      (node (ref "T12") (pin "C") (pinfunction "C_C") (pintype "passive"))
    )
    (net (code "220") (name "Net-(PC6-PadA)") (class "Default")
      (node (ref "PC6") (pin "A") (pinfunction "A_A") (pintype "passive"))
      (node (ref "R13") (pin "2") (pinfunction "2_2") (pintype "passive"))
    )
    (net (code "221") (name "Net-(PC6-PadB)") (class "Default")
      (node (ref "PC6") (pin "B") (pinfunction "B_B") (pintype "passive"))
      (node (ref "T13") (pin "C") (pinfunction "C_C") (pintype "passive"))
    )
    (net (code "222") (name "Net-(PC7-PadA)") (class "Default")
      (node (ref "PC7") (pin "A") (pinfunction "A_A") (pintype "passive"))
      (node (ref "R14") (pin "2") (pinfunction "2_2") (pintype "passive"))
    )
    (net (code "223") (name "Net-(PC7-PadB)") (class "Default")
      (node (ref "PC7") (pin "B") (pinfunction "B_B") (pintype "passive"))
      (node (ref "T14") (pin "C") (pinfunction "C_C") (pintype "passive"))
    )
    (net (code "224") (name "Net-(PC8-PadA)") (class "Default")
      (node (ref "PC8") (pin "A") (pinfunction "A_A") (pintype "passive"))
      (node (ref "R15") (pin "2") (pinfunction "2_2") (pintype "passive"))
    )
    (net (code "225") (name "Net-(PC8-PadB)") (class "Default")
      (node (ref "PC8") (pin "B") (pinfunction "B_B") (pintype "passive"))
      (node (ref "T15") (pin "C") (pinfunction "C_C") (pintype "passive"))
    )
    (net (code "226") (name "Net-(PC9-PadA)") (class "Default")
      (node (ref "PC9") (pin "A") (pinfunction "A_A") (pintype "passive"))
      (node (ref "R16") (pin "2") (pinfunction "2_2") (pintype "passive"))
    )
    (net (code "227") (name "Net-(PC9-PadB)") (class "Default")
      (node (ref "PC9") (pin "B") (pinfunction "B_B") (pintype "passive"))
      (node (ref "T16") (pin "C") (pinfunction "C_C") (pintype "passive"))
    )
    (net (code "228") (name "Net-(PC10-PadA)") (class "Default")
      (node (ref "PC10") (pin "A") (pinfunction "A_A") (pintype "passive"))
      (node (ref "R17") (pin "2") (pinfunction "2_2") (pintype "passive"))
    )
    (net (code "229") (name "Net-(PC10-PadB)") (class "Default")
      (node (ref "PC10") (pin "B") (pinfunction "B_B") (pintype "passive"))
      (node (ref "T17") (pin "C") (pinfunction "C_C") (pintype "passive"))
    )
    (net (code "230") (name "Net-(PC11-PadA)") (class "Default")
      (node (ref "PC11") (pin "A") (pinfunction "A_A") (pintype "passive"))
      (node (ref "R18") (pin "2") (pinfunction "2_2") (pintype "passive"))
    )
    (net (code "231") (name "Net-(PC11-PadB)") (class "Default")
      (node (ref "PC11") (pin "B") (pinfunction "B_B") (pintype "passive"))
      (node (ref "T18") (pin "C") (pinfunction "C_C") (pintype "passive"))
    )
    (net (code "232") (name "Net-(R67-Pad2)") (class "Default")
      (node (ref "R67") (pin "2") (pinfunction "2_2") (pintype "passive"))
      (node (ref "SC0") (pin "A") (pinfunction "A_A") (pintype "passive"))
    )
    (net (code "233") (name "Net-(R68-Pad2)") (class "Default")
      (node (ref "R68") (pin "2") (pinfunction "2_2") (pintype "passive"))
      (node (ref "SC1") (pin "A") (pinfunction "A_A") (pintype "passive"))
    )
    (net (code "234") (name "Net-(R69-Pad2)") (class "Default")
      (node (ref "R69") (pin "2") (pinfunction "2_2") (pintype "passive"))
      (node (ref "SC2") (pin "A") (pinfunction "A_A") (pintype "passive"))
    )
    (net (code "235") (name "Net-(R70-Pad2)") (class "Default")
      (node (ref "R70") (pin "2") (pinfunction "2_2") (pintype "passive"))
      (node (ref "SC3") (pin "A") (pinfunction "A_A") (pintype "passive"))
    )
    (net (code "236") (name "Net-(R71-Pad2)") (class "Default")
      (node (ref "R71") (pin "2") (pinfunction "2_2") (pintype "passive"))
      (node (ref "SC4") (pin "A") (pinfunction "A_A") (pintype "passive"))
    )
    (net (code "237") (name "Net-(R75-Pad2)") (class "Default")
      (node (ref "R75") (pin "2") (pinfunction "2_2") (pintype "passive"))
      (node (ref "RUN") (pin "A") (pinfunction "A_A") (pintype "passive"))
    )
    (net (code "238") (name "Net-(R79-Pad2)") (class "Default")
      (node (ref "R79") (pin "2") (pinfunction "2_2") (pintype "passive"))
      (node (ref "WORDCOUNT") (pin "A") (pinfunction "A_A") (pintype "passive"))
    )
    (net (code "239") (name "Net-(R83-Pad2)") (class "Default")
      (node (ref "R83") (pin "2") (pinfunction "2_2") (pintype "passive"))
      (node (ref "TAD") (pin "A") (pinfunction "A_A") (pintype "passive"))
    )
    (net (code "240") (name "Net-(RUN-PadB)") (class "Default")
      (node (ref "RUN") (pin "B") (pinfunction "B_B") (pintype "passive"))
      (node (ref "T75") (pin "C") (pinfunction "C_C") (pintype "passive"))
    )
    (net (code "241") (name "Net-(SC0-PadB)") (class "Default")
      (node (ref "SC0") (pin "B") (pinfunction "B_B") (pintype "passive"))
      (node (ref "T67") (pin "C") (pinfunction "C_C") (pintype "passive"))
    )
    (net (code "242") (name "Net-(SC1-PadB)") (class "Default")
      (node (ref "SC1") (pin "B") (pinfunction "B_B") (pintype "passive"))
      (node (ref "T68") (pin "C") (pinfunction "C_C") (pintype "passive"))
    )
    (net (code "243") (name "Net-(SC2-PadB)") (class "Default")
      (node (ref "SC2") (pin "B") (pinfunction "B_B") (pintype "passive"))
      (node (ref "T69") (pin "C") (pinfunction "C_C") (pintype "passive"))
    )
    (net (code "244") (name "Net-(SC3-PadB)") (class "Default")
      (node (ref "SC3") (pin "B") (pinfunction "B_B") (pintype "passive"))
      (node (ref "T70") (pin "C") (pinfunction "C_C") (pintype "passive"))
    )
    (net (code "245") (name "Net-(SC4-PadB)") (class "Default")
      (node (ref "SC4") (pin "B") (pinfunction "B_B") (pintype "passive"))
      (node (ref "T71") (pin "C") (pinfunction "C_C") (pintype "passive"))
    )
    (net (code "246") (name "Net-(T79-PadC)") (class "Default")
      (node (ref "T79") (pin "C") (pinfunction "C_C") (pintype "passive"))
      (node (ref "WORDCOUNT") (pin "B") (pinfunction "B_B") (pintype "passive"))
    )
    (net (code "247") (name "Net-(T83-PadC)") (class "Default")
      (node (ref "T83") (pin "C") (pinfunction "C_C") (pintype "passive"))
      (node (ref "TAD") (pin "B") (pinfunction "B_B") (pintype "passive"))
    )
    (net (code "248") (name "OPR") (class "Default")
      (node (ref "D40") (pin "16") (pinfunction "16_16") (pintype "passive"))
      (node (ref "F40BOT") (pin "11") (pinfunction "1_11") (pintype "passive"))
      (node (ref "T89") (pin "B") (pinfunction "B_B") (pintype "passive"))
    )
    (net (code "249") (name "PAUSE") (class "Default")
      (node (ref "D40") (pin "31") (pinfunction "31_31") (pintype "passive"))
      (node (ref "F40TOP") (pin "17") (pinfunction "1_17") (pintype "passive"))
      (node (ref "T74") (pin "B") (pinfunction "B_B") (pintype "passive"))
    )
    (net (code "250") (name "PC0") (class "Default")
      (node (ref "D40TOP") (pin "1") (pinfunction "1_1") (pintype "passive"))
      (node (ref "E40") (pin "1") (pinfunction "1_1") (pintype "passive"))
      (node (ref "T7") (pin "B") (pinfunction "B_B") (pintype "passive"))
    )
    (net (code "251") (name "PC1") (class "Default")
      (node (ref "D40BOT") (pin "5") (pinfunction "1_5") (pintype "passive"))
      (node (ref "E40") (pin "10") (pinfunction "10_10") (pintype "passive"))
      (node (ref "T8") (pin "B") (pinfunction "B_B") (pintype "passive"))
    )
    (net (code "252") (name "PC2") (class "Default")
      (node (ref "D40TOP") (pin "6") (pinfunction "1_6") (pintype "passive"))
      (node (ref "E40") (pin "11") (pinfunction "11_11") (pintype "passive"))
      (node (ref "T9") (pin "B") (pinfunction "B_B") (pintype "passive"))
    )
    (net (code "253") (name "PC3") (class "Default")
      (node (ref "D40BOT") (pin "14") (pinfunction "1_14") (pintype "passive"))
      (node (ref "E40") (pin "24") (pinfunction "24_24") (pintype "passive"))
      (node (ref "T10") (pin "B") (pinfunction "B_B") (pintype "passive"))
    )
    (net (code "254") (name "PC4") (class "Default")
      (node (ref "D40TOP") (pin "14") (pinfunction "1_14") (pintype "passive"))
      (node (ref "E40") (pin "25") (pinfunction "25_25") (pintype "passive"))
      (node (ref "T11") (pin "B") (pinfunction "B_B") (pintype "passive"))
    )
    (net (code "255") (name "PC5") (class "Default")
      (node (ref "D40BOT") (pin "19") (pinfunction "1_19") (pintype "passive"))
      (node (ref "E40") (pin "34") (pinfunction "34_34") (pintype "passive"))
      (node (ref "T12") (pin "B") (pinfunction "B_B") (pintype "passive"))
    )
    (net (code "256") (name "PC6") (class "Default")
      (node (ref "E40TOP") (pin "1") (pinfunction "1_1") (pintype "passive"))
      (node (ref "F40") (pin "1") (pinfunction "1_1") (pintype "passive"))
      (node (ref "T13") (pin "B") (pinfunction "B_B") (pintype "passive"))
    )
    (net (code "257") (name "PC7") (class "Default")
      (node (ref "E40BOT") (pin "5") (pinfunction "1_5") (pintype "passive"))
      (node (ref "F40") (pin "10") (pinfunction "10_10") (pintype "passive"))
      (node (ref "T14") (pin "B") (pinfunction "B_B") (pintype "passive"))
    )
    (net (code "258") (name "PC8") (class "Default")
      (node (ref "E40TOP") (pin "6") (pinfunction "1_6") (pintype "passive"))
      (node (ref "F40") (pin "11") (pinfunction "11_11") (pintype "passive"))
      (node (ref "T15") (pin "B") (pinfunction "B_B") (pintype "passive"))
    )
    (net (code "259") (name "PC9") (class "Default")
      (node (ref "E40BOT") (pin "14") (pinfunction "1_14") (pintype "passive"))
      (node (ref "F40") (pin "24") (pinfunction "24_24") (pintype "passive"))
      (node (ref "T16") (pin "B") (pinfunction "B_B") (pintype "passive"))
    )
    (net (code "260") (name "PC10") (class "Default")
      (node (ref "E40TOP") (pin "14") (pinfunction "1_14") (pintype "passive"))
      (node (ref "F40") (pin "25") (pinfunction "25_25") (pintype "passive"))
      (node (ref "T17") (pin "B") (pinfunction "B_B") (pintype "passive"))
    )
    (net (code "261") (name "PC11") (class "Default")
      (node (ref "E40BOT") (pin "19") (pinfunction "1_19") (pintype "passive"))
      (node (ref "F40") (pin "34") (pinfunction "34_34") (pintype "passive"))
      (node (ref "T18") (pin "B") (pinfunction "B_B") (pintype "passive"))
    )
    (net (code "262") (name "RUN") (class "Default")
      (node (ref "D40") (pin "33") (pinfunction "33_33") (pintype "passive"))
      (node (ref "F40TOP") (pin "18") (pinfunction "1_18") (pintype "passive"))
      (node (ref "T75") (pin "B") (pinfunction "B_B") (pintype "passive"))
    )
    (net (code "263") (name "S$1") (class "Default")
      (node (ref "D40") (pin "23") (pinfunction "23_23") (pintype "passive"))
      (node (ref "F40TOP") (pin "13") (pinfunction "1_13") (pintype "passive"))
    )
    (net (code "264") (name "SC0") (class "Default")
      (node (ref "C40") (pin "9") (pinfunction "9_9") (pintype "passive"))
      (node (ref "C40TOP") (pin "5") (pinfunction "1_5") (pintype "passive"))
      (node (ref "T67") (pin "B") (pinfunction "B_B") (pintype "passive"))
    )
    (net (code "265") (name "SC1") (class "Default")
      (node (ref "C40") (pin "2") (pinfunction "2_2") (pintype "passive"))
      (node (ref "C40BOT") (pin "1") (pinfunction "1_1") (pintype "passive"))
      (node (ref "T68") (pin "B") (pinfunction "B_B") (pintype "passive"))
    )
    (net (code "266") (name "SC2") (class "Default")
      (node (ref "C40") (pin "23") (pinfunction "23_23") (pintype "passive"))
      (node (ref "C40TOP") (pin "13") (pinfunction "1_13") (pintype "passive"))
      (node (ref "T69") (pin "B") (pinfunction "B_B") (pintype "passive"))
    )
    (net (code "267") (name "SC3") (class "Default")
      (node (ref "C40") (pin "12") (pinfunction "12_12") (pintype "passive"))
      (node (ref "C40BOT") (pin "6") (pinfunction "1_6") (pintype "passive"))
      (node (ref "T70") (pin "B") (pinfunction "B_B") (pintype "passive"))
    )
    (net (code "268") (name "SC4") (class "Default")
      (node (ref "C40") (pin "33") (pinfunction "33_33") (pintype "passive"))
      (node (ref "C40TOP") (pin "18") (pinfunction "1_18") (pintype "passive"))
      (node (ref "T71") (pin "B") (pinfunction "B_B") (pintype "passive"))
    )
    (net (code "269") (name "TAD") (class "Default")
      (node (ref "D40") (pin "4") (pinfunction "4_4") (pintype "passive"))
      (node (ref "F40BOT") (pin "2") (pinfunction "1_2") (pintype "passive"))
      (node (ref "T83") (pin "B") (pinfunction "B_B") (pintype "passive"))
    )
    (net (code "270") (name "WC") (class "Default")
      (node (ref "D40") (pin "30") (pinfunction "30_30") (pintype "passive"))
      (node (ref "F40BOT") (pin "17") (pinfunction "1_17") (pintype "passive"))
      (node (ref "T79") (pin "B") (pinfunction "B_B") (pintype "passive"))
    )
    (net (code "271") (name "unconnected-(C40-Pad3)") (class "Default")
      (node (ref "C40") (pin "3") (pinfunction "3_3") (pintype "passive"))
    )
    (net (code "272") (name "unconnected-(C40-Pad4)") (class "Default")
      (node (ref "C40") (pin "4") (pinfunction "4_4") (pintype "passive"))
    )
    (net (code "273") (name "unconnected-(C40-Pad5)") (class "Default")
      (node (ref "C40") (pin "5") (pinfunction "5_5") (pintype "passive"))
    )
    (net (code "274") (name "unconnected-(C40-Pad6)") (class "Default")
      (node (ref "C40") (pin "6") (pinfunction "6_6") (pintype "passive"))
    )
    (net (code "275") (name "unconnected-(C40-Pad7)") (class "Default")
      (node (ref "C40") (pin "7") (pinfunction "7_7") (pintype "passive"))
    )
    (net (code "276") (name "unconnected-(C40-Pad8)") (class "Default")
      (node (ref "C40") (pin "8") (pinfunction "8_8") (pintype "passive"))
    )
    (net (code "277") (name "unconnected-(C40-Pad13)") (class "Default")
      (node (ref "C40") (pin "13") (pinfunction "13_13") (pintype "passive"))
    )
    (net (code "278") (name "unconnected-(C40-Pad14)") (class "Default")
      (node (ref "C40") (pin "14") (pinfunction "14_14") (pintype "passive"))
    )
    (net (code "279") (name "unconnected-(C40-Pad15)") (class "Default")
      (node (ref "C40") (pin "15") (pinfunction "15_15") (pintype "passive"))
    )
    (net (code "280") (name "unconnected-(C40-Pad16)") (class "Default")
      (node (ref "C40") (pin "16") (pinfunction "16_16") (pintype "passive"))
    )
    (net (code "281") (name "unconnected-(C40-Pad21)") (class "Default")
      (node (ref "C40") (pin "21") (pinfunction "21_21") (pintype "passive"))
    )
    (net (code "282") (name "unconnected-(C40-Pad22)") (class "Default")
      (node (ref "C40") (pin "22") (pinfunction "22_22") (pintype "passive"))
    )
    (net (code "283") (name "unconnected-(C40-Pad26)") (class "Default")
      (node (ref "C40") (pin "26") (pinfunction "26_26") (pintype "passive"))
    )
    (net (code "284") (name "unconnected-(C40-Pad27)") (class "Default")
      (node (ref "C40") (pin "27") (pinfunction "27_27") (pintype "passive"))
    )
    (net (code "285") (name "unconnected-(C40-Pad29)") (class "Default")
      (node (ref "C40") (pin "29") (pinfunction "29_29") (pintype "passive"))
    )
    (net (code "286") (name "unconnected-(C40-Pad30)") (class "Default")
      (node (ref "C40") (pin "30") (pinfunction "30_30") (pintype "passive"))
    )
    (net (code "287") (name "unconnected-(C40-Pad31)") (class "Default")
      (node (ref "C40") (pin "31") (pinfunction "31_31") (pintype "passive"))
    )
    (net (code "288") (name "unconnected-(C40-Pad32)") (class "Default")
      (node (ref "C40") (pin "32") (pinfunction "32_32") (pintype "passive"))
    )
    (net (code "289") (name "unconnected-(D40-Pad1)") (class "Default")
      (node (ref "D40") (pin "1") (pinfunction "1_1") (pintype "passive"))
    )
    (net (code "290") (name "unconnected-(D40-Pad3)") (class "Default")
      (node (ref "D40") (pin "3") (pinfunction "3_3") (pintype "passive"))
    )
    (net (code "291") (name "unconnected-(D40-Pad5)") (class "Default")
      (node (ref "D40") (pin "5") (pinfunction "5_5") (pintype "passive"))
    )
    (net (code "292") (name "unconnected-(D40-Pad7)") (class "Default")
      (node (ref "D40") (pin "7") (pinfunction "7_7") (pintype "passive"))
    )
    (net (code "293") (name "unconnected-(D40-Pad9)") (class "Default")
      (node (ref "D40") (pin "9") (pinfunction "9_9") (pintype "passive"))
    )
    (net (code "294") (name "unconnected-(D40-Pad11)") (class "Default")
      (node (ref "D40") (pin "11") (pinfunction "11_11") (pintype "passive"))
    )
    (net (code "295") (name "unconnected-(D40-Pad13)") (class "Default")
      (node (ref "D40") (pin "13") (pinfunction "13_13") (pintype "passive"))
    )
    (net (code "296") (name "unconnected-(D40-Pad15)") (class "Default")
      (node (ref "D40") (pin "15") (pinfunction "15_15") (pintype "passive"))
    )
    (net (code "297") (name "unconnected-(D40-Pad21)") (class "Default")
      (node (ref "D40") (pin "21") (pinfunction "21_21") (pintype "passive"))
    )
    (net (code "298") (name "unconnected-(D40-Pad25)") (class "Default")
      (node (ref "D40") (pin "25") (pinfunction "25_25") (pintype "passive"))
    )
    (net (code "299") (name "unconnected-(D40-Pad27)") (class "Default")
      (node (ref "D40") (pin "27") (pinfunction "27_27") (pintype "passive"))
    )
    (net (code "300") (name "unconnected-(D40-Pad29)") (class "Default")
      (node (ref "D40") (pin "29") (pinfunction "29_29") (pintype "passive"))
    )
  )
)
